# rev2.net
KiCad netlist of a schematic drawn in EAGLE
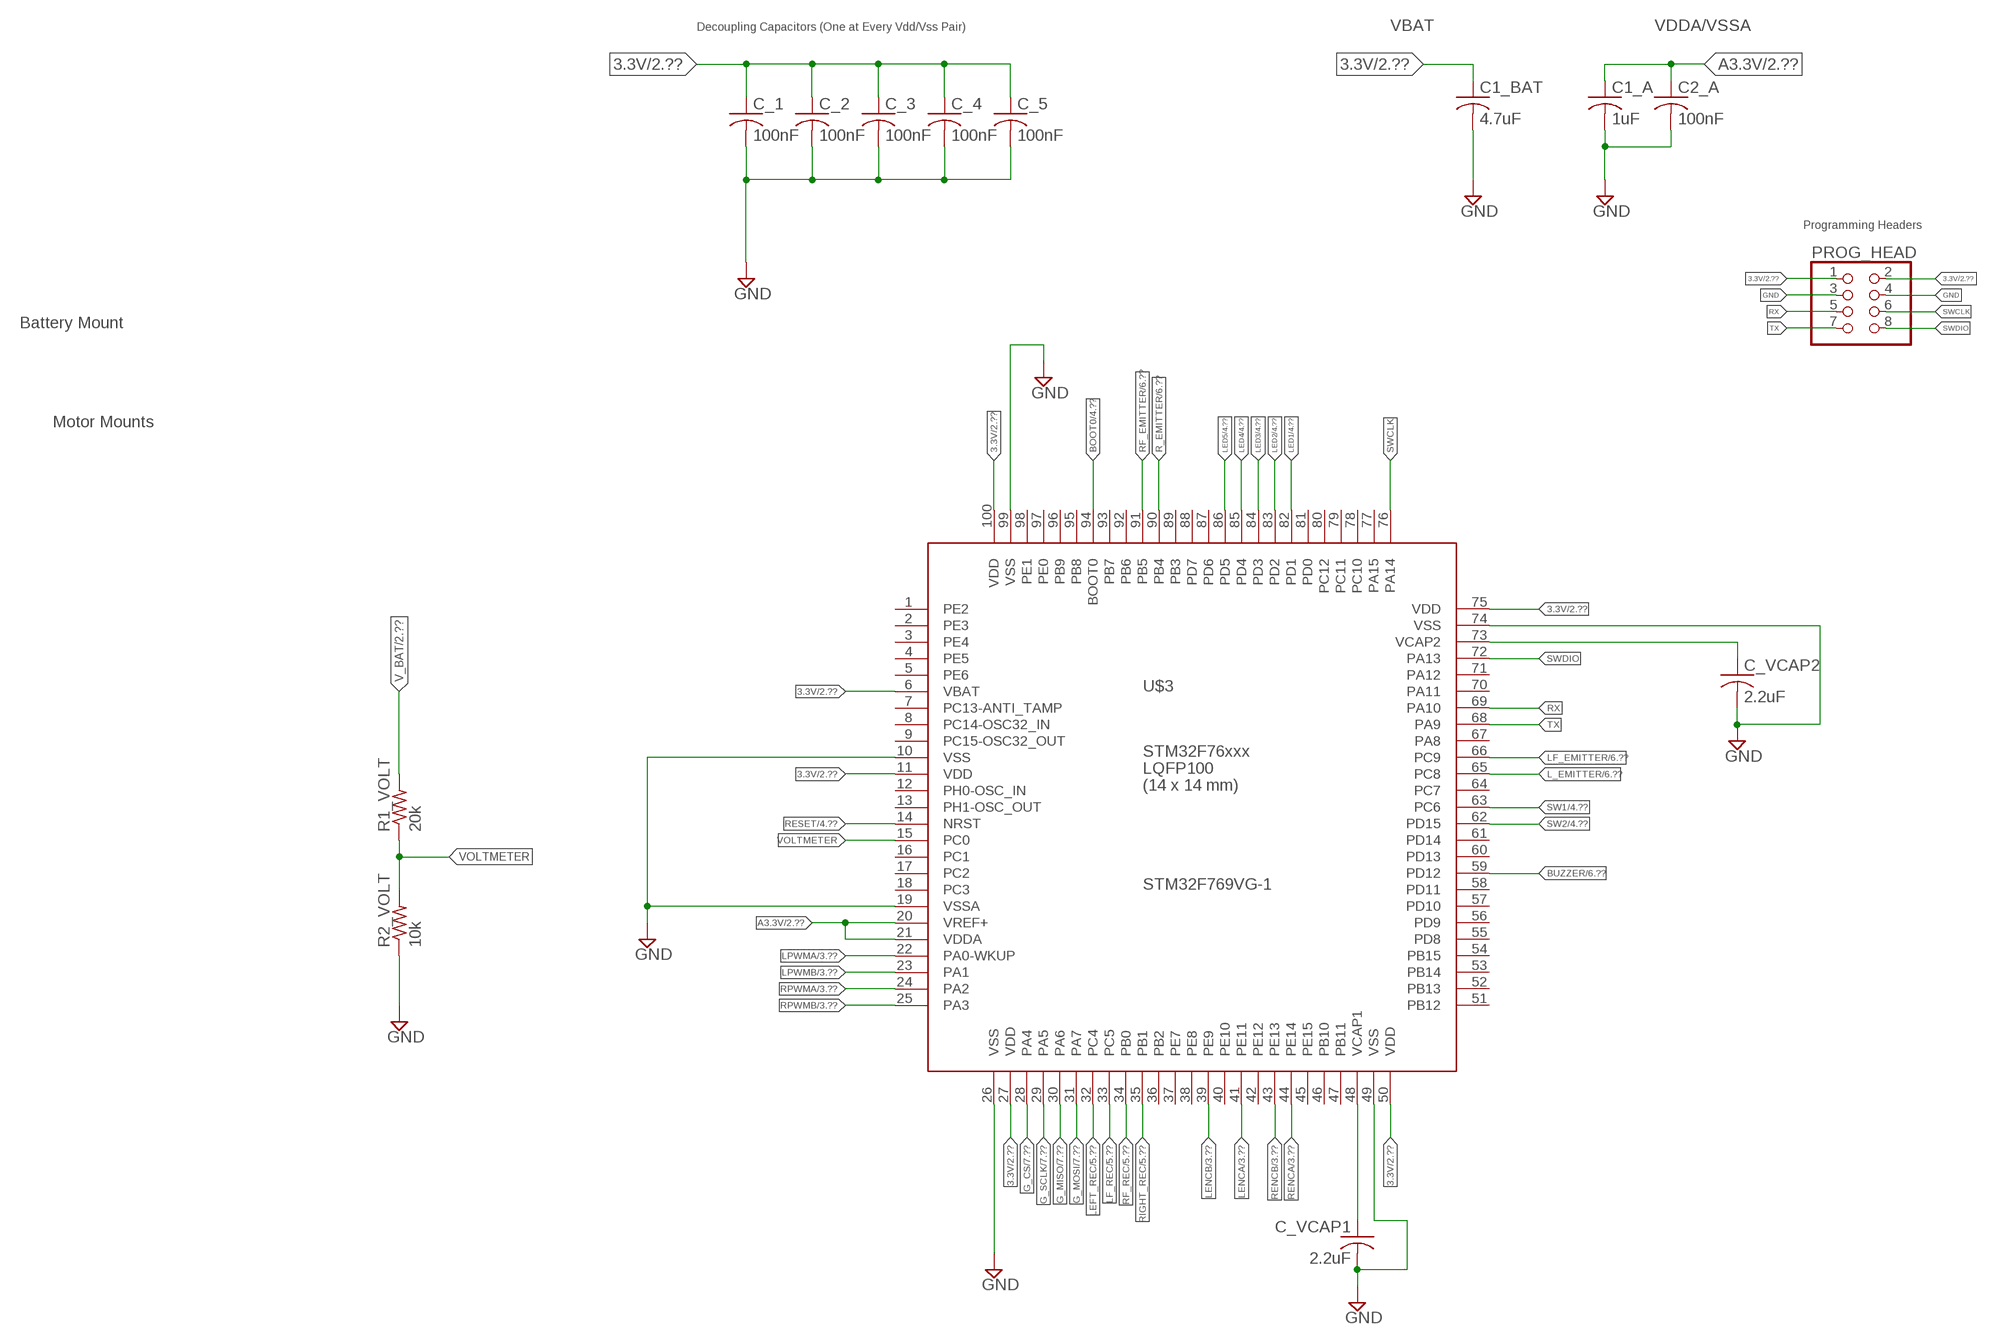
[diagram p0: schematic, sheet 1]
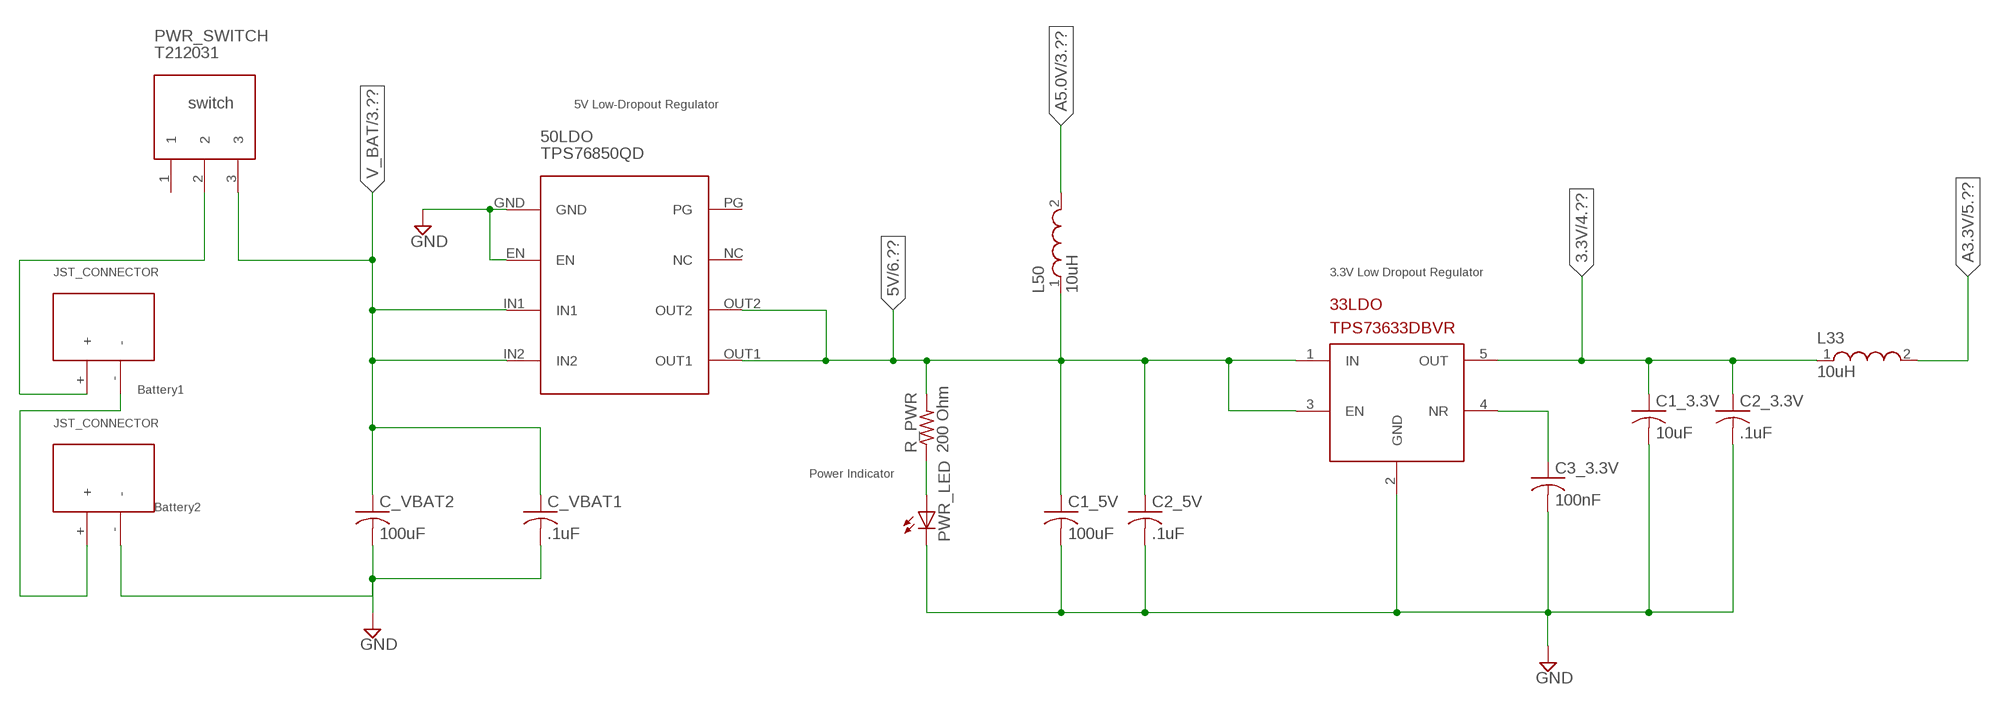
[diagram p1: schematic, sheet 2]
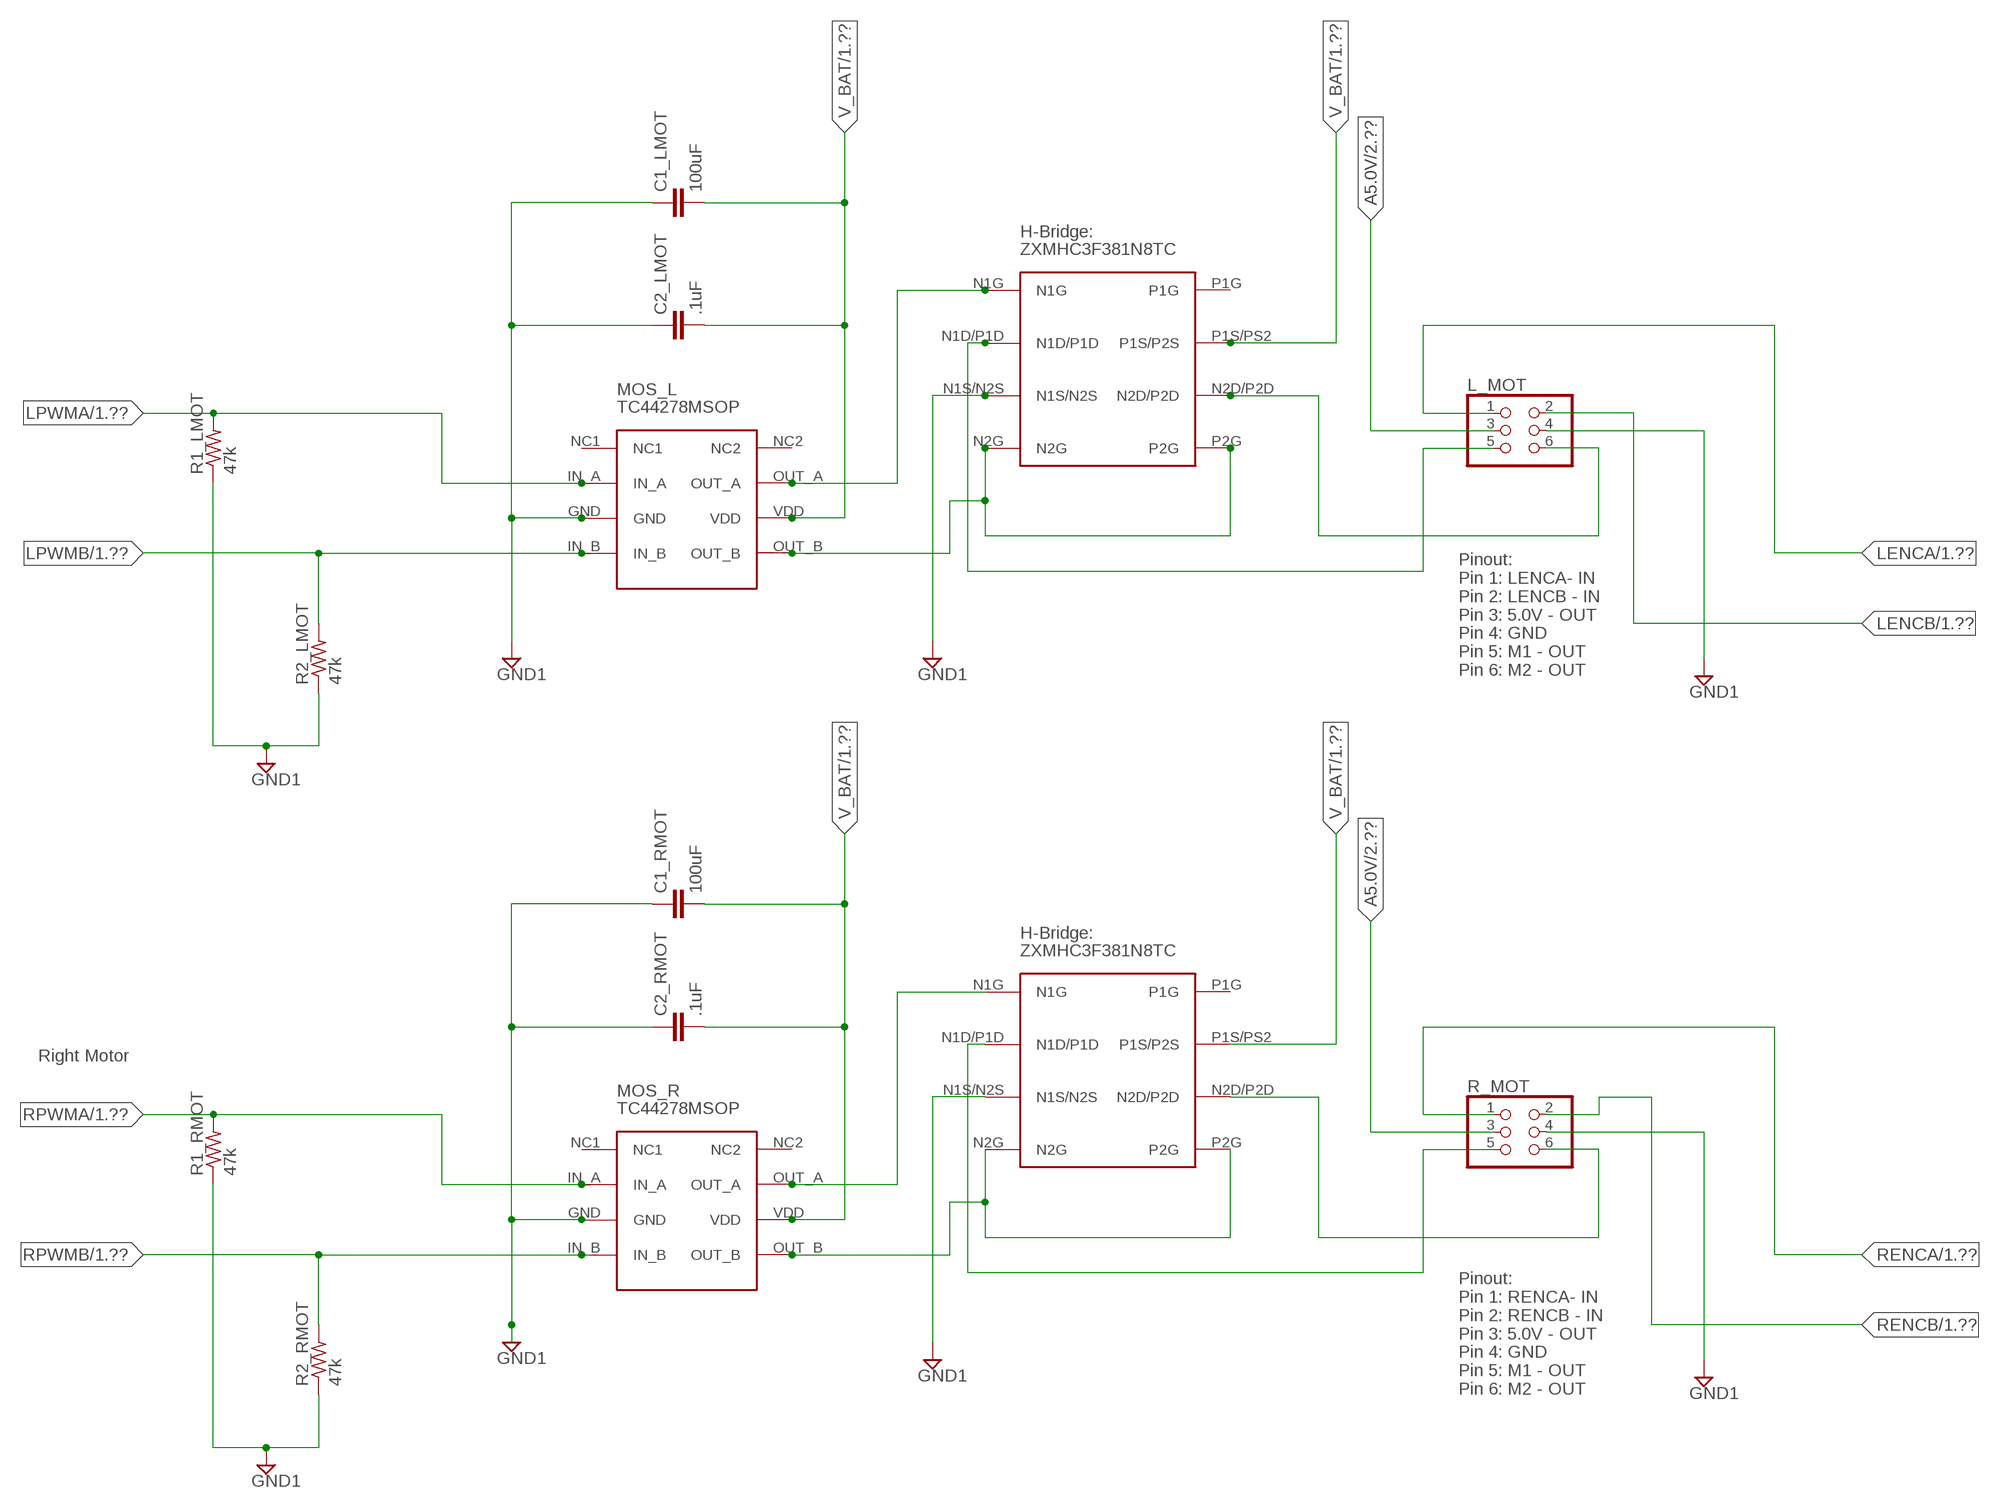
[diagram p2: schematic, sheet 3]
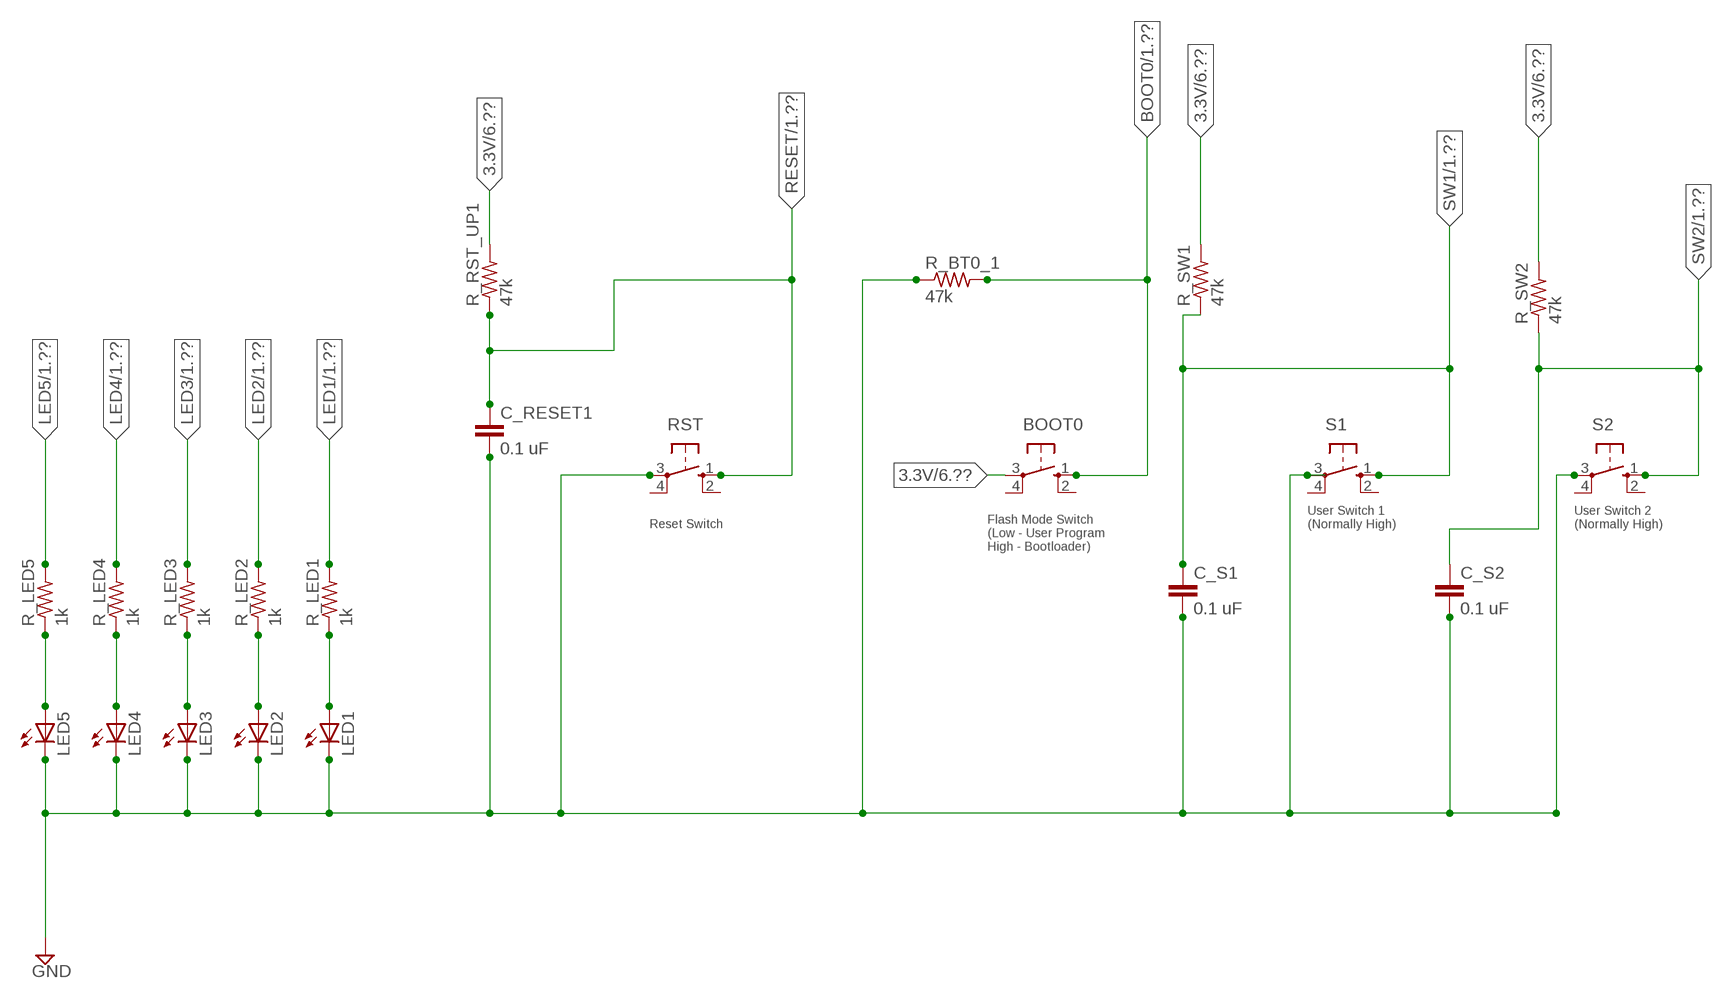
[diagram p3: schematic, sheet 4]
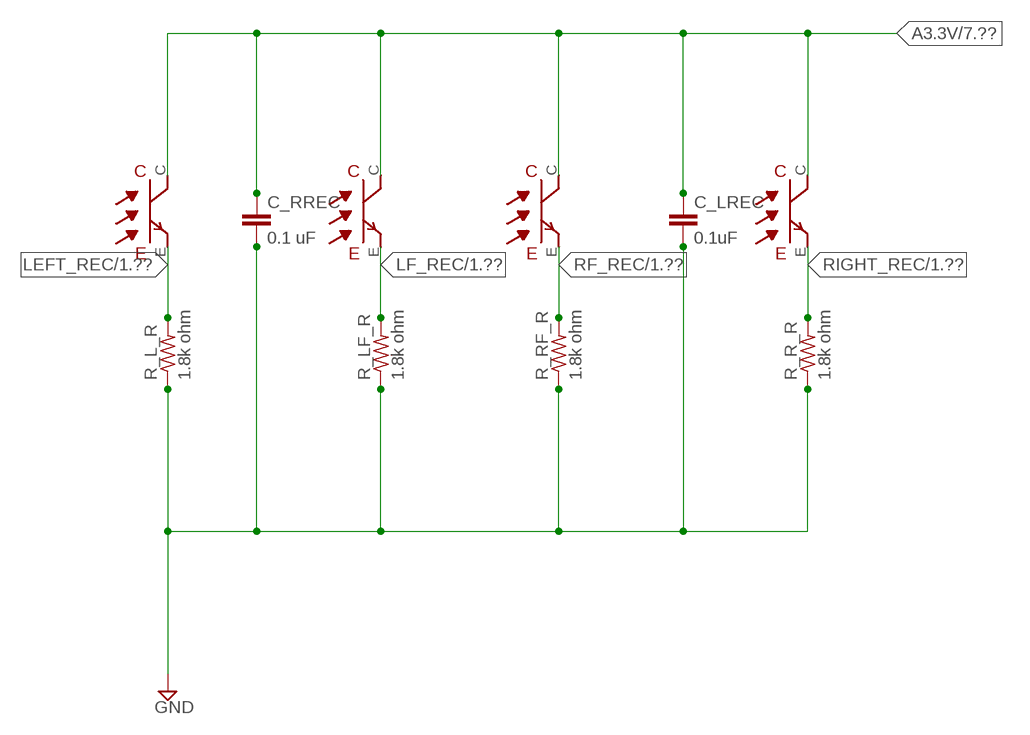
[diagram p4: schematic, sheet 5]
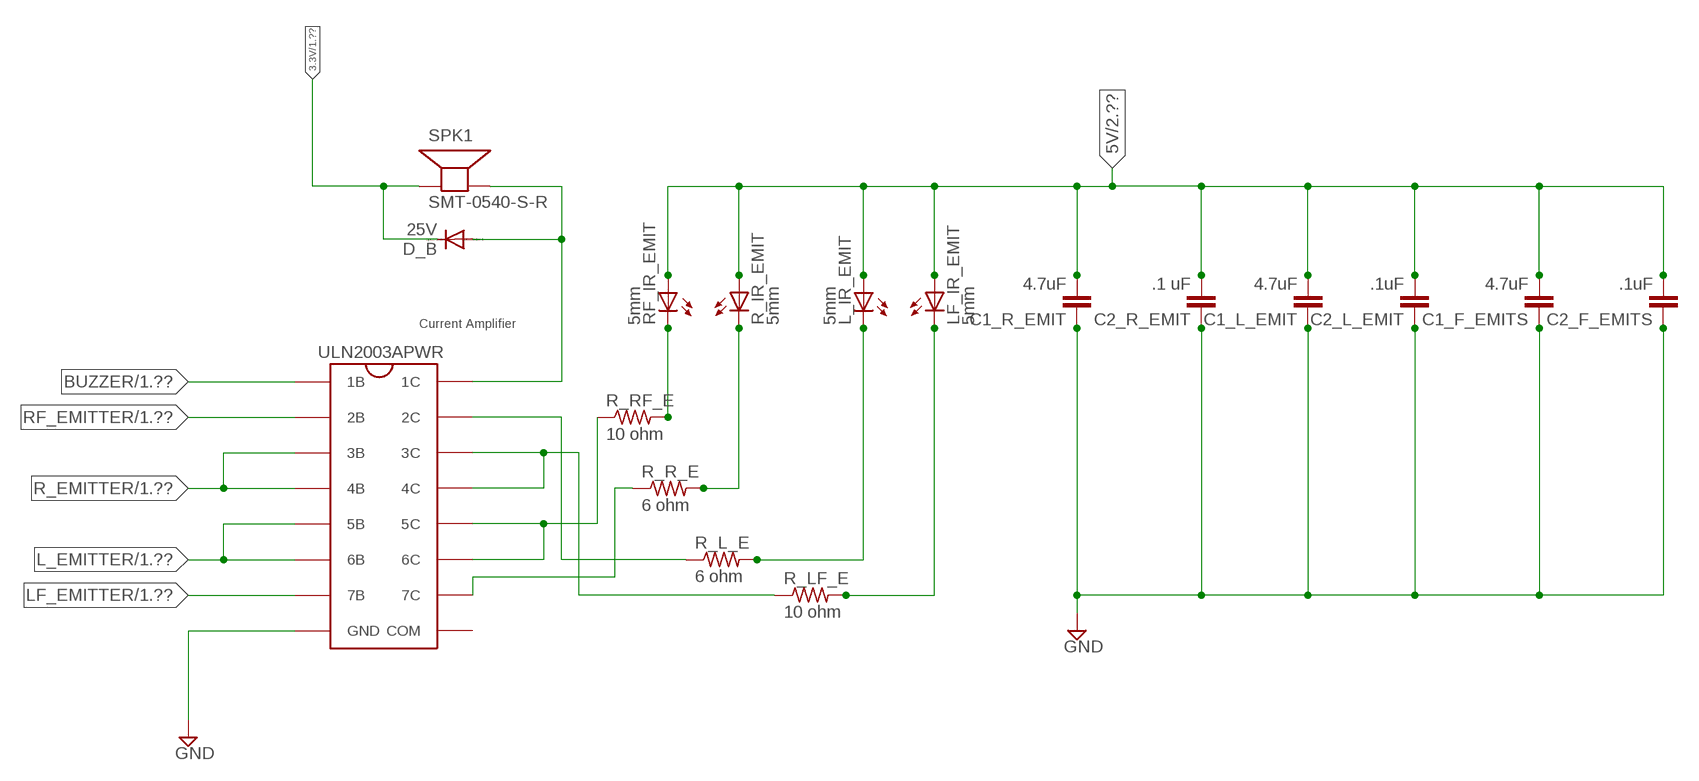
[diagram p5: schematic, sheet 6]
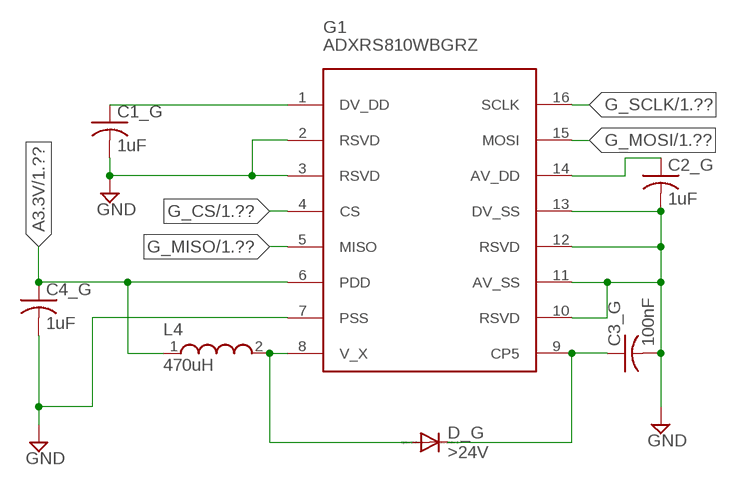
[diagram p6: schematic, sheet 7]

(export (version "E")
  (design (tool "Eeschema 10.0.6"))
  (components
    (comp (ref "C1_LMOT")
      (value "100uF")
      (footprint "eagle-import:C0805")
      (libsource (lib "eagle-import") (part "C-EUC0805"))
    )
    (comp (ref "C1_RMOT")
      (value "100uF")
      (footprint "eagle-import:C0805")
      (libsource (lib "eagle-import") (part "C-EUC0805"))
    )
    (comp (ref "C2_LMOT")
      (value ".1uF")
      (footprint "eagle-import:C0805")
      (libsource (lib "eagle-import") (part "C-EUC0805"))
    )
    (comp (ref "C2_RMOT")
      (value ".1uF")
      (footprint "eagle-import:C0805")
      (libsource (lib "eagle-import") (part "C-EUC0805"))
    )
    (comp (ref "HB_L")
      (value "ZXMHC3F381N8TC")
      (footprint "eagle-import:8-SOIC")
      (libsource (lib "eagle-import") (part "ZXMHC3F381N8TC"))
    )
    (comp (ref "HB_R")
      (value "ZXMHC3F381N8TC")
      (footprint "eagle-import:8-SOIC")
      (libsource (lib "eagle-import") (part "ZXMHC3F381N8TC"))
    )
    (comp (ref "L_MOT")
      (value "PINHD-2X3")
      (footprint "eagle-import:2X03")
      (libsource (lib "eagle-import") (part "PINHD-2X3"))
    )
    (comp (ref "MOS_L")
      (value "TC44278MSOP")
      (footprint "eagle-import:TC44278MSOP")
      (libsource (lib "eagle-import") (part "TC44278MSOP"))
    )
    (comp (ref "MOS_R")
      (value "TC44278MSOP")
      (footprint "eagle-import:TC44278MSOP")
      (libsource (lib "eagle-import") (part "TC44278MSOP"))
    )
    (comp (ref "R1_LMOT")
      (value "47k")
      (footprint "eagle-import:R0603")
      (libsource (lib "eagle-import") (part "R-US_R0603"))
    )
    (comp (ref "R1_RMOT")
      (value "47k")
      (footprint "eagle-import:R0603")
      (libsource (lib "eagle-import") (part "R-US_R0603"))
    )
    (comp (ref "R2_LMOT")
      (value "47k")
      (footprint "eagle-import:R0603")
      (libsource (lib "eagle-import") (part "R-US_R0603"))
    )
    (comp (ref "R2_RMOT")
      (value "47k")
      (footprint "eagle-import:R0603")
      (libsource (lib "eagle-import") (part "R-US_R0603"))
    )
    (comp (ref "R_MOT")
      (value "PINHD-2X3")
      (footprint "eagle-import:2X03")
      (libsource (lib "eagle-import") (part "PINHD-2X3"))
    )
    (comp (ref "C1_F_EMITS")
      (value "4.7uF")
      (footprint "eagle-import:C0603")
      (libsource (lib "eagle-import") (part "resistor_C-EUC0603"))
    )
    (comp (ref "C1_L_EMIT")
      (value "4.7uF")
      (footprint "eagle-import:C0603")
      (libsource (lib "eagle-import") (part "resistor_C-EUC0603"))
    )
    (comp (ref "C1_R_EMIT")
      (value "4.7uF")
      (footprint "eagle-import:C0603")
      (libsource (lib "eagle-import") (part "resistor_C-EUC0603"))
    )
    (comp (ref "C2_F_EMITS")
      (value ".1uF")
      (footprint "eagle-import:C0603")
      (libsource (lib "eagle-import") (part "resistor_C-EUC0603"))
    )
    (comp (ref "C2_L_EMIT")
      (value ".1uF")
      (footprint "eagle-import:C0603")
      (libsource (lib "eagle-import") (part "resistor_C-EUC0603"))
    )
    (comp (ref "C2_R_EMIT")
      (value ".1 uF")
      (footprint "eagle-import:C0603")
      (libsource (lib "eagle-import") (part "resistor_C-EUC0603"))
    )
    (comp (ref "D_B")
      (value "25V")
      (footprint "eagle-import:SOD123")
      (libsource (lib "eagle-import") (part "DIODE-SOD123"))
    )
    (comp (ref "LF_IR_EMIT")
      (value "5mm")
      (footprint "eagle-import:LED5MM")
      (libsource (lib "eagle-import") (part "LED5MM"))
    )
    (comp (ref "L_IR_EMIT")
      (value "5mm")
      (footprint "eagle-import:LED5MM")
      (libsource (lib "eagle-import") (part "LED5MM"))
    )
    (comp (ref "RF_IR_EMIT")
      (value "5mm")
      (footprint "eagle-import:LED5MM")
      (libsource (lib "eagle-import") (part "LED5MM"))
    )
    (comp (ref "R_IR_EMIT")
      (value "5mm")
      (footprint "eagle-import:LED5MM")
      (libsource (lib "eagle-import") (part "LED5MM"))
    )
    (comp (ref "R_LF_E")
      (value "10 ohm")
      (footprint "eagle-import:R0603")
      (libsource (lib "eagle-import") (part "R-US_R0603"))
    )
    (comp (ref "R_L_E")
      (value "6 ohm")
      (footprint "eagle-import:R0603")
      (libsource (lib "eagle-import") (part "R-US_R0603"))
    )
    (comp (ref "R_RF_E")
      (value "10 ohm")
      (footprint "eagle-import:R0603")
      (libsource (lib "eagle-import") (part "R-US_R0603"))
    )
    (comp (ref "R_R_E")
      (value "6 ohm")
      (footprint "eagle-import:R0603")
      (libsource (lib "eagle-import") (part "R-US_R0603"))
    )
    (comp (ref "SPK1")
      (value "SMT-0540-S-R")
      (footprint "eagle-import:SMT-0540-S-R")
      (fields (field (name "MF") "PUI Audio"))
      (libsource (lib "eagle-import") (part "SMT-0540-S-R"))
    )
    (comp (ref "U$9")
      (value "ULN2003APWR")
      (footprint "eagle-import:ULN2003APWR")
      (libsource (lib "eagle-import") (part "ULN2003APWR"))
    )
    (comp (ref "BOOT0")
      (value "10-XX")
      (footprint "eagle-import:B3F-10XX")
      (fields (field (name "MPN") "B3F-1000"))
      (libsource (lib "eagle-import") (part "10-XX"))
    )
    (comp (ref "C_RESET1")
      (value "0.1 uF")
      (footprint "eagle-import:C0603")
      (libsource (lib "eagle-import") (part "resistor_C-EUC0603"))
    )
    (comp (ref "C_S1")
      (value "0.1 uF")
      (footprint "eagle-import:C0603")
      (libsource (lib "eagle-import") (part "resistor_C-EUC0603"))
    )
    (comp (ref "C_S2")
      (value "0.1 uF")
      (footprint "eagle-import:C0603")
      (libsource (lib "eagle-import") (part "resistor_C-EUC0603"))
    )
    (comp (ref "LED1")
      (value "LEDCHIPLED_0805")
      (footprint "eagle-import:CHIPLED_0805")
      (libsource (lib "eagle-import") (part "LEDCHIPLED_0805"))
    )
    (comp (ref "LED2")
      (value "LEDCHIPLED_0805")
      (footprint "eagle-import:CHIPLED_0805")
      (libsource (lib "eagle-import") (part "LEDCHIPLED_0805"))
    )
    (comp (ref "LED3")
      (value "LEDCHIPLED_0805")
      (footprint "eagle-import:CHIPLED_0805")
      (libsource (lib "eagle-import") (part "LEDCHIPLED_0805"))
    )
    (comp (ref "LED4")
      (value "LEDCHIPLED_0805")
      (footprint "eagle-import:CHIPLED_0805")
      (libsource (lib "eagle-import") (part "LEDCHIPLED_0805"))
    )
    (comp (ref "LED5")
      (value "LEDCHIPLED_0805")
      (footprint "eagle-import:CHIPLED_0805")
      (libsource (lib "eagle-import") (part "LEDCHIPLED_0805"))
    )
    (comp (ref "RST")
      (value "10-XX")
      (footprint "eagle-import:B3F-10XX")
      (fields (field (name "MPN") "B3F-1000"))
      (libsource (lib "eagle-import") (part "10-XX"))
    )
    (comp (ref "R_BT0_1")
      (value "47k")
      (footprint "eagle-import:R0603")
      (libsource (lib "eagle-import") (part "R-US_R0603"))
    )
    (comp (ref "R_LED1")
      (value "1k")
      (footprint "eagle-import:R0603")
      (libsource (lib "eagle-import") (part "R-US_R0603"))
    )
    (comp (ref "R_LED2")
      (value "1k")
      (footprint "eagle-import:R0603")
      (libsource (lib "eagle-import") (part "R-US_R0603"))
    )
    (comp (ref "R_LED3")
      (value "1k")
      (footprint "eagle-import:R0603")
      (libsource (lib "eagle-import") (part "R-US_R0603"))
    )
    (comp (ref "R_LED4")
      (value "1k")
      (footprint "eagle-import:R0603")
      (libsource (lib "eagle-import") (part "R-US_R0603"))
    )
    (comp (ref "R_LED5")
      (value "1k")
      (footprint "eagle-import:R0603")
      (libsource (lib "eagle-import") (part "R-US_R0603"))
    )
    (comp (ref "R_RST_UP1")
      (value "47k")
      (footprint "eagle-import:R0603")
      (libsource (lib "eagle-import") (part "R-US_R0603"))
    )
    (comp (ref "R_SW1")
      (value "47k")
      (footprint "eagle-import:R0603")
      (libsource (lib "eagle-import") (part "R-US_R0603"))
    )
    (comp (ref "R_SW2")
      (value "47k")
      (footprint "eagle-import:R0603")
      (libsource (lib "eagle-import") (part "R-US_R0603"))
    )
    (comp (ref "S1")
      (value "10-XX")
      (footprint "eagle-import:B3F-10XX")
      (fields (field (name "MPN") "B3F-1000"))
      (libsource (lib "eagle-import") (part "10-XX"))
    )
    (comp (ref "S2")
      (value "10-XX")
      (footprint "eagle-import:B3F-10XX")
      (fields (field (name "MPN") "B3F-1000"))
      (libsource (lib "eagle-import") (part "10-XX"))
    )
    (comp (ref "C1_A")
      (value "1uF")
      (footprint "eagle-import:C0603")
      (libsource (lib "eagle-import") (part "C-USC0603"))
    )
    (comp (ref "C1_BAT")
      (value "4.7uF")
      (footprint "eagle-import:C0603")
      (libsource (lib "eagle-import") (part "C-USC0603"))
    )
    (comp (ref "C2_A")
      (value "100nF")
      (footprint "eagle-import:C0603")
      (libsource (lib "eagle-import") (part "C-USC0603"))
    )
    (comp (ref "C_1")
      (value "100nF")
      (footprint "eagle-import:C0603")
      (libsource (lib "eagle-import") (part "C-USC0603"))
    )
    (comp (ref "C_2")
      (value "100nF")
      (footprint "eagle-import:C0603")
      (libsource (lib "eagle-import") (part "C-USC0603"))
    )
    (comp (ref "C_3")
      (value "100nF")
      (footprint "eagle-import:C0603")
      (libsource (lib "eagle-import") (part "C-USC0603"))
    )
    (comp (ref "C_4")
      (value "100nF")
      (footprint "eagle-import:C0603")
      (libsource (lib "eagle-import") (part "C-USC0603"))
    )
    (comp (ref "C_5")
      (value "100nF")
      (footprint "eagle-import:C0603")
      (libsource (lib "eagle-import") (part "C-USC0603"))
    )
    (comp (ref "C_VCAP1")
      (value "2.2uF")
      (footprint "eagle-import:C0603")
      (libsource (lib "eagle-import") (part "C-USC0603"))
    )
    (comp (ref "C_VCAP2")
      (value "2.2uF")
      (footprint "eagle-import:C0603")
      (libsource (lib "eagle-import") (part "C-USC0603"))
    )
    (comp (ref "PROG_HEAD")
      (value "PINHD-2X4")
      (footprint "eagle-import:2X04")
      (libsource (lib "eagle-import") (part "PINHD-2X4"))
    )
    (comp (ref "R1_VOLT")
      (value "20k")
      (footprint "eagle-import:R0603")
      (libsource (lib "eagle-import") (part "R-US_R0603"))
    )
    (comp (ref "R2_VOLT")
      (value "10k")
      (footprint "eagle-import:R0603")
      (libsource (lib "eagle-import") (part "R-US_R0603"))
    )
    (comp (ref "U$2")
      (value "MOTOR")
      (footprint "eagle-import:MOTOR_MOUNT")
      (libsource (lib "eagle-import") (part "MOTOR"))
    )
    (comp (ref "U$3")
      (value "STM32F769VG-1")
      (footprint "eagle-import:LQFP100")
      (libsource (lib "eagle-import") (part "STM32F769VG-1"))
    )
    (comp (ref "U$5")
      (value "MOTOR")
      (footprint "eagle-import:MOTOR_MOUNT")
      (libsource (lib "eagle-import") (part "MOTOR"))
    )
    (comp (ref "C1_G")
      (value "1uF")
      (footprint "eagle-import:C0603")
      (libsource (lib "eagle-import") (part "C-USC0603"))
    )
    (comp (ref "C2_G")
      (value "1uF")
      (footprint "eagle-import:C0603")
      (libsource (lib "eagle-import") (part "C-USC0603"))
    )
    (comp (ref "C3_G")
      (value "100nF")
      (footprint "eagle-import:C0603")
      (libsource (lib "eagle-import") (part "C-USC0603"))
    )
    (comp (ref "C4_G")
      (value "1uF")
      (footprint "eagle-import:C0603")
      (libsource (lib "eagle-import") (part "C-USC0603"))
    )
    (comp (ref "D_G")
      (value ">24V")
      (footprint "eagle-import:SOD123")
      (libsource (lib "eagle-import") (part "DIODE-SOD123"))
    )
    (comp (ref "G1")
      (value "ADXRS810")
      (footprint "eagle-import:SOIC-16")
      (libsource (lib "eagle-import") (part "ADXRS810"))
    )
    (comp (ref "L4")
      (value "470uH")
      (footprint "eagle-import:WE-MI_0805")
      (libsource (lib "eagle-import") (part "WE-MI_0805"))
    )
    (comp (ref "33LDO")
      (value "TPS73633DBVR")
      (footprint "eagle-import:SOT23-DBV")
      (fields (field (name "MF") "Texas Instruments"))
      (libsource (lib "eagle-import") (part "TPS73633DBVR"))
    )
    (comp (ref "50LDO")
      (value "TPS76850QD")
      (footprint "eagle-import:8-SOIC(SMT)")
      (libsource (lib "eagle-import") (part "TPS76850"))
    )
    (comp (ref "C1_3.3V")
      (value "10uF")
      (footprint "eagle-import:C0603")
      (libsource (lib "eagle-import") (part "resistor_C-USC0603"))
    )
    (comp (ref "C1_5V")
      (value "100uF")
      (footprint "eagle-import:C0603")
      (libsource (lib "eagle-import") (part "resistor_C-USC0603"))
    )
    (comp (ref "C2_3.3V")
      (value ".1uF")
      (footprint "eagle-import:C0603")
      (libsource (lib "eagle-import") (part "resistor_C-USC0603"))
    )
    (comp (ref "C2_5V")
      (value ".1uF")
      (footprint "eagle-import:C0603")
      (libsource (lib "eagle-import") (part "resistor_C-USC0603"))
    )
    (comp (ref "C3_3.3V")
      (value "100nF")
      (footprint "eagle-import:C0603")
      (libsource (lib "eagle-import") (part "resistor_C-USC0603"))
    )
    (comp (ref "C_VBAT1")
      (value ".1uF")
      (footprint "eagle-import:C0603")
      (libsource (lib "eagle-import") (part "resistor_C-USC0603"))
    )
    (comp (ref "C_VBAT2")
      (value "100uF")
      (footprint "eagle-import:C1206")
      (libsource (lib "eagle-import") (part "resistor_C-USC1206"))
    )
    (comp (ref "L33")
      (value "10uH")
      (footprint "eagle-import:WE-MI_0805")
      (libsource (lib "eagle-import") (part "WE-MI_0805"))
    )
    (comp (ref "L50")
      (value "10uH")
      (footprint "eagle-import:WE-MI_0805")
      (libsource (lib "eagle-import") (part "WE-MI_0805"))
    )
    (comp (ref "PWR_LED")
      (value "LEDCHIPLED_0805")
      (footprint "eagle-import:CHIPLED_0805")
      (libsource (lib "eagle-import") (part "LEDCHIPLED_0805"))
    )
    (comp (ref "PWR_SWITCH")
      (value "T212031")
      (footprint "eagle-import:T212031")
      (libsource (lib "eagle-import") (part "T212031"))
    )
    (comp (ref "R_PWR")
      (value "200 Ohm")
      (footprint "eagle-import:R0603")
      (libsource (lib "eagle-import") (part "R-US_R0603"))
    )
    (comp (ref "U$7")
      (value "JST_CONNECTOR_FEMALE")
      (footprint "eagle-import:JST_CONNECTOR_FEMALE")
      (libsource (lib "eagle-import") (part "JST_CONNECTOR_FEMALE"))
    )
    (comp (ref "U$8")
      (value "JST_CONNECTOR_FEMALE")
      (footprint "eagle-import:JST_CONNECTOR_FEMALE")
      (libsource (lib "eagle-import") (part "JST_CONNECTOR_FEMALE"))
    )
    (comp (ref "C_LREC")
      (value "0.1uF")
      (footprint "eagle-import:C0603")
      (libsource (lib "eagle-import") (part "resistor_C-EUC0603"))
    )
    (comp (ref "C_RREC")
      (value "0.1 uF")
      (footprint "eagle-import:C0603")
      (libsource (lib "eagle-import") (part "resistor_C-EUC0603"))
    )
    (comp (ref "LF_REC")
      (value "RECEIVER")
      (footprint "eagle-import:RECEIVER")
      (libsource (lib "eagle-import") (part "RECEIVER"))
    )
    (comp (ref "L_REC")
      (value "RECEIVER")
      (footprint "eagle-import:RECEIVER")
      (libsource (lib "eagle-import") (part "RECEIVER"))
    )
    (comp (ref "RF_REC")
      (value "RECEIVER")
      (footprint "eagle-import:RECEIVER")
      (libsource (lib "eagle-import") (part "RECEIVER"))
    )
    (comp (ref "R_LF_R")
      (value "1.8k ohm")
      (footprint "eagle-import:R0603")
      (libsource (lib "eagle-import") (part "R-US_R0603"))
    )
    (comp (ref "R_L_R")
      (value "1.8k ohm")
      (footprint "eagle-import:R0603")
      (libsource (lib "eagle-import") (part "R-US_R0603"))
    )
    (comp (ref "R_REC")
      (value "RECEIVER")
      (footprint "eagle-import:RECEIVER")
      (libsource (lib "eagle-import") (part "RECEIVER"))
    )
    (comp (ref "R_RF_R")
      (value "1.8k ohm")
      (footprint "eagle-import:R0603")
      (libsource (lib "eagle-import") (part "R-US_R0603"))
    )
    (comp (ref "R_R_R")
      (value "1.8k ohm")
      (footprint "eagle-import:R0603")
      (libsource (lib "eagle-import") (part "R-US_R0603"))
    )
  )
  (nets
    (net (code "1") (name "3.3V") (class "Default")
      (node (ref "33LDO") (pin "5") (pinfunction "OUT_5") (pintype "bidirectional"))
      (node (ref "BOOT0") (pin "3") (pinfunction "P_3") (pintype "passive"))
      (node (ref "C1_3.3V") (pin "1") (pinfunction "1_1") (pintype "passive"))
      (node (ref "C1_BAT") (pin "1") (pinfunction "1_1") (pintype "passive"))
      (node (ref "C2_3.3V") (pin "1") (pinfunction "1_1") (pintype "passive"))
      (node (ref "C_1") (pin "1") (pinfunction "1_1") (pintype "passive"))
      (node (ref "C_2") (pin "1") (pinfunction "1_1") (pintype "passive"))
      (node (ref "C_3") (pin "1") (pinfunction "1_1") (pintype "passive"))
      (node (ref "C_4") (pin "1") (pinfunction "1_1") (pintype "passive"))
      (node (ref "C_5") (pin "1") (pinfunction "1_1") (pintype "passive"))
      (node (ref "D_B") (pin "C") (pinfunction "C_C") (pintype "passive"))
      (node (ref "L33") (pin "1") (pinfunction "1_1") (pintype "passive"))
      (node (ref "PROG_HEAD") (pin "1") (pinfunction "1_1") (pintype "passive"))
      (node (ref "PROG_HEAD") (pin "2") (pinfunction "2_2") (pintype "passive"))
      (node (ref "R_RST_UP1") (pin "2") (pinfunction "2_2") (pintype "passive"))
      (node (ref "R_SW1") (pin "2") (pinfunction "2_2") (pintype "passive"))
      (node (ref "R_SW2") (pin "2") (pinfunction "2_2") (pintype "passive"))
      (node (ref "SPK1") (pin "-") (pinfunction "+_-") (pintype "passive"))
      (node (ref "U$3") (pin "100") (pinfunction "VDD_100") (pintype "bidirectional"))
      (node (ref "U$3") (pin "11") (pinfunction "VDD_11") (pintype "bidirectional"))
      (node (ref "U$3") (pin "27") (pinfunction "VDD_27") (pintype "bidirectional"))
      (node (ref "U$3") (pin "50") (pinfunction "VDD_50") (pintype "bidirectional"))
      (node (ref "U$3") (pin "6") (pinfunction "VBAT_6") (pintype "bidirectional"))
      (node (ref "U$3") (pin "75") (pinfunction "VDD_75") (pintype "bidirectional"))
    )
    (net (code "2") (name "5V") (class "Default")
      (node (ref "33LDO") (pin "1") (pinfunction "IN_1") (pintype "bidirectional"))
      (node (ref "33LDO") (pin "3") (pinfunction "EN_3") (pintype "bidirectional"))
      (node (ref "50LDO") (pin "OUT1") (pinfunction "OUT1_OUT1") (pintype "bidirectional"))
      (node (ref "50LDO") (pin "OUT2") (pinfunction "OUT2_OUT2") (pintype "bidirectional"))
      (node (ref "C1_5V") (pin "1") (pinfunction "1_1") (pintype "passive"))
      (node (ref "C1_F_EMITS") (pin "2") (pinfunction "2_2") (pintype "passive"))
      (node (ref "C1_L_EMIT") (pin "2") (pinfunction "2_2") (pintype "passive"))
      (node (ref "C1_R_EMIT") (pin "2") (pinfunction "2_2") (pintype "passive"))
      (node (ref "C2_5V") (pin "1") (pinfunction "1_1") (pintype "passive"))
      (node (ref "C2_F_EMITS") (pin "2") (pinfunction "2_2") (pintype "passive"))
      (node (ref "C2_L_EMIT") (pin "2") (pinfunction "2_2") (pintype "passive"))
      (node (ref "C2_R_EMIT") (pin "2") (pinfunction "2_2") (pintype "passive"))
      (node (ref "L50") (pin "1") (pinfunction "1_1") (pintype "passive"))
      (node (ref "LF_IR_EMIT") (pin "A") (pinfunction "A_A") (pintype "passive"))
      (node (ref "L_IR_EMIT") (pin "A") (pinfunction "A_A") (pintype "passive"))
      (node (ref "RF_IR_EMIT") (pin "A") (pinfunction "A_A") (pintype "passive"))
      (node (ref "R_IR_EMIT") (pin "A") (pinfunction "A_A") (pintype "passive"))
      (node (ref "R_PWR") (pin "2") (pinfunction "2_2") (pintype "passive"))
    )
    (net (code "3") (name "A3.3V") (class "Default")
      (node (ref "C1_A") (pin "1") (pinfunction "1_1") (pintype "passive"))
      (node (ref "C2_A") (pin "1") (pinfunction "1_1") (pintype "passive"))
      (node (ref "C4_G") (pin "1") (pinfunction "1_1") (pintype "passive"))
      (node (ref "C_LREC") (pin "1") (pinfunction "1_1") (pintype "passive"))
      (node (ref "C_RREC") (pin "1") (pinfunction "1_1") (pintype "passive"))
      (node (ref "G1") (pin "6") (pinfunction "PDD_6") (pintype "bidirectional"))
      (node (ref "L33") (pin "2") (pinfunction "2_2") (pintype "passive"))
      (node (ref "L4") (pin "1") (pinfunction "1_1") (pintype "passive"))
      (node (ref "LF_REC") (pin "C") (pinfunction "C_C") (pintype "bidirectional"))
      (node (ref "L_REC") (pin "C") (pinfunction "C_C") (pintype "bidirectional"))
      (node (ref "RF_REC") (pin "C") (pinfunction "C_C") (pintype "bidirectional"))
      (node (ref "R_REC") (pin "C") (pinfunction "C_C") (pintype "bidirectional"))
      (node (ref "U$3") (pin "20") (pinfunction "VREF+_20") (pintype "bidirectional"))
      (node (ref "U$3") (pin "21") (pinfunction "VDDA_21") (pintype "bidirectional"))
    )
    (net (code "4") (name "A5.0V") (class "Default")
      (node (ref "L50") (pin "2") (pinfunction "2_2") (pintype "passive"))
      (node (ref "L_MOT") (pin "3") (pinfunction "3_3") (pintype "passive"))
      (node (ref "R_MOT") (pin "3") (pinfunction "3_3") (pintype "passive"))
    )
    (net (code "5") (name "BOOT0") (class "Default")
      (node (ref "BOOT0") (pin "1") (pinfunction "S_1") (pintype "passive"))
      (node (ref "R_BT0_1") (pin "2") (pinfunction "2_2") (pintype "passive"))
      (node (ref "U$3") (pin "94") (pinfunction "BOOT0_94") (pintype "bidirectional"))
    )
    (net (code "6") (name "BUZZER") (class "Default")
      (node (ref "U$3") (pin "59") (pinfunction "PD12_59") (pintype "bidirectional"))
      (node (ref "U$9") (pin "1B") (pinfunction "1B_1B") (pintype "bidirectional"))
    )
    (net (code "7") (name "GND") (class "Default")
      (node (ref "33LDO") (pin "2") (pinfunction "GND_2") (pintype "bidirectional"))
      (node (ref "50LDO") (pin "EN") (pinfunction "EN_EN") (pintype "bidirectional"))
      (node (ref "50LDO") (pin "GND") (pinfunction "GND_GND") (pintype "bidirectional"))
      (node (ref "C1_3.3V") (pin "2") (pinfunction "2_2") (pintype "passive"))
      (node (ref "C1_5V") (pin "2") (pinfunction "2_2") (pintype "passive"))
      (node (ref "C1_A") (pin "2") (pinfunction "2_2") (pintype "passive"))
      (node (ref "C1_BAT") (pin "2") (pinfunction "2_2") (pintype "passive"))
      (node (ref "C1_F_EMITS") (pin "1") (pinfunction "1_1") (pintype "passive"))
      (node (ref "C1_G") (pin "2") (pinfunction "2_2") (pintype "passive"))
      (node (ref "C1_LMOT") (pin "1") (pinfunction "1_1") (pintype "passive"))
      (node (ref "C1_L_EMIT") (pin "1") (pinfunction "1_1") (pintype "passive"))
      (node (ref "C1_RMOT") (pin "1") (pinfunction "1_1") (pintype "passive"))
      (node (ref "C1_R_EMIT") (pin "1") (pinfunction "1_1") (pintype "passive"))
      (node (ref "C2_3.3V") (pin "2") (pinfunction "2_2") (pintype "passive"))
      (node (ref "C2_5V") (pin "2") (pinfunction "2_2") (pintype "passive"))
      (node (ref "C2_A") (pin "2") (pinfunction "2_2") (pintype "passive"))
      (node (ref "C2_F_EMITS") (pin "1") (pinfunction "1_1") (pintype "passive"))
      (node (ref "C2_G") (pin "2") (pinfunction "2_2") (pintype "passive"))
      (node (ref "C2_LMOT") (pin "1") (pinfunction "1_1") (pintype "passive"))
      (node (ref "C2_L_EMIT") (pin "1") (pinfunction "1_1") (pintype "passive"))
      (node (ref "C2_RMOT") (pin "1") (pinfunction "1_1") (pintype "passive"))
      (node (ref "C2_R_EMIT") (pin "1") (pinfunction "1_1") (pintype "passive"))
      (node (ref "C3_3.3V") (pin "2") (pinfunction "2_2") (pintype "passive"))
      (node (ref "C3_G") (pin "2") (pinfunction "2_2") (pintype "passive"))
      (node (ref "C4_G") (pin "2") (pinfunction "2_2") (pintype "passive"))
      (node (ref "C_1") (pin "2") (pinfunction "2_2") (pintype "passive"))
      (node (ref "C_2") (pin "2") (pinfunction "2_2") (pintype "passive"))
      (node (ref "C_3") (pin "2") (pinfunction "2_2") (pintype "passive"))
      (node (ref "C_4") (pin "2") (pinfunction "2_2") (pintype "passive"))
      (node (ref "C_5") (pin "2") (pinfunction "2_2") (pintype "passive"))
      (node (ref "C_LREC") (pin "2") (pinfunction "2_2") (pintype "passive"))
      (node (ref "C_RESET1") (pin "2") (pinfunction "2_2") (pintype "passive"))
      (node (ref "C_RREC") (pin "2") (pinfunction "2_2") (pintype "passive"))
      (node (ref "C_S1") (pin "2") (pinfunction "2_2") (pintype "passive"))
      (node (ref "C_S2") (pin "2") (pinfunction "2_2") (pintype "passive"))
      (node (ref "C_VBAT1") (pin "2") (pinfunction "2_2") (pintype "passive"))
      (node (ref "C_VBAT2") (pin "2") (pinfunction "2_2") (pintype "passive"))
      (node (ref "C_VCAP1") (pin "2") (pinfunction "2_2") (pintype "passive"))
      (node (ref "C_VCAP2") (pin "2") (pinfunction "2_2") (pintype "passive"))
      (node (ref "G1") (pin "10") (pinfunction "RSVD_10") (pintype "bidirectional"))
      (node (ref "G1") (pin "11") (pinfunction "AV_SS_11") (pintype "bidirectional"))
      (node (ref "G1") (pin "12") (pinfunction "RSVD_12") (pintype "bidirectional"))
      (node (ref "G1") (pin "13") (pinfunction "DV_SS_13") (pintype "bidirectional"))
      (node (ref "G1") (pin "2") (pinfunction "RSVD_2") (pintype "bidirectional"))
      (node (ref "G1") (pin "3") (pinfunction "RSVD_3") (pintype "bidirectional"))
      (node (ref "G1") (pin "7") (pinfunction "PSS_7") (pintype "bidirectional"))
      (node (ref "HB_L") (pin "N1S/N2S") (pinfunction "N1S/N2S_N1S/N2S") (pintype "bidirectional"))
      (node (ref "HB_R") (pin "N1S/N2S") (pinfunction "N1S/N2S_N1S/N2S") (pintype "bidirectional"))
      (node (ref "LED1") (pin "C") (pinfunction "C_C") (pintype "passive"))
      (node (ref "LED2") (pin "C") (pinfunction "C_C") (pintype "passive"))
      (node (ref "LED3") (pin "C") (pinfunction "C_C") (pintype "passive"))
      (node (ref "LED4") (pin "C") (pinfunction "C_C") (pintype "passive"))
      (node (ref "LED5") (pin "C") (pinfunction "C_C") (pintype "passive"))
      (node (ref "L_MOT") (pin "4") (pinfunction "4_4") (pintype "passive"))
      (node (ref "MOS_L") (pin "GND") (pinfunction "GND_GND") (pintype "bidirectional"))
      (node (ref "MOS_R") (pin "GND") (pinfunction "GND_GND") (pintype "bidirectional"))
      (node (ref "PROG_HEAD") (pin "3") (pinfunction "3_3") (pintype "passive"))
      (node (ref "PROG_HEAD") (pin "4") (pinfunction "4_4") (pintype "passive"))
      (node (ref "PWR_LED") (pin "C") (pinfunction "C_C") (pintype "passive"))
      (node (ref "R1_LMOT") (pin "1") (pinfunction "1_1") (pintype "passive"))
      (node (ref "R1_RMOT") (pin "1") (pinfunction "1_1") (pintype "passive"))
      (node (ref "R2_LMOT") (pin "1") (pinfunction "1_1") (pintype "passive"))
      (node (ref "R2_RMOT") (pin "1") (pinfunction "1_1") (pintype "passive"))
      (node (ref "R2_VOLT") (pin "1") (pinfunction "1_1") (pintype "passive"))
      (node (ref "RST") (pin "3") (pinfunction "P_3") (pintype "passive"))
      (node (ref "R_BT0_1") (pin "1") (pinfunction "1_1") (pintype "passive"))
      (node (ref "R_LF_R") (pin "1") (pinfunction "1_1") (pintype "passive"))
      (node (ref "R_L_R") (pin "1") (pinfunction "1_1") (pintype "passive"))
      (node (ref "R_MOT") (pin "4") (pinfunction "4_4") (pintype "passive"))
      (node (ref "R_RF_R") (pin "1") (pinfunction "1_1") (pintype "passive"))
      (node (ref "R_R_R") (pin "1") (pinfunction "1_1") (pintype "passive"))
      (node (ref "S1") (pin "3") (pinfunction "P_3") (pintype "passive"))
      (node (ref "S2") (pin "3") (pinfunction "P_3") (pintype "passive"))
      (node (ref "U$3") (pin "10") (pinfunction "VSS_10") (pintype "bidirectional"))
      (node (ref "U$3") (pin "19") (pinfunction "VSSA_19") (pintype "bidirectional"))
      (node (ref "U$3") (pin "26") (pinfunction "VSS_26") (pintype "bidirectional"))
      (node (ref "U$3") (pin "49") (pinfunction "VSS_49") (pintype "bidirectional"))
      (node (ref "U$3") (pin "74") (pinfunction "VSS_74") (pintype "bidirectional"))
      (node (ref "U$3") (pin "99") (pinfunction "VSS_99") (pintype "bidirectional"))
      (node (ref "U$8") (pin "-") (pinfunction "-_-") (pintype "bidirectional"))
      (node (ref "U$9") (pin "GND") (pinfunction "GND_GND") (pintype "bidirectional"))
    )
    (net (code "8") (name "G_CS") (class "Default")
      (node (ref "G1") (pin "4") (pinfunction "CS_4") (pintype "bidirectional"))
      (node (ref "U$3") (pin "28") (pinfunction "PA4_28") (pintype "bidirectional"))
    )
    (net (code "9") (name "G_MISO") (class "Default")
      (node (ref "G1") (pin "5") (pinfunction "MISO_5") (pintype "bidirectional"))
      (node (ref "U$3") (pin "30") (pinfunction "PA6_30") (pintype "bidirectional"))
    )
    (net (code "10") (name "G_MOSI") (class "Default")
      (node (ref "G1") (pin "15") (pinfunction "MOSI_15") (pintype "bidirectional"))
      (node (ref "U$3") (pin "31") (pinfunction "PA7_31") (pintype "bidirectional"))
    )
    (net (code "11") (name "G_SCLK") (class "Default")
      (node (ref "G1") (pin "16") (pinfunction "SCLK_16") (pintype "bidirectional"))
      (node (ref "U$3") (pin "29") (pinfunction "PA5_29") (pintype "bidirectional"))
    )
    (net (code "12") (name "LED1") (class "Default")
      (node (ref "R_LED1") (pin "2") (pinfunction "2_2") (pintype "passive"))
      (node (ref "U$3") (pin "82") (pinfunction "PD1_82") (pintype "bidirectional"))
    )
    (net (code "13") (name "LED2") (class "Default")
      (node (ref "R_LED2") (pin "2") (pinfunction "2_2") (pintype "passive"))
      (node (ref "U$3") (pin "83") (pinfunction "PD2_83") (pintype "bidirectional"))
    )
    (net (code "14") (name "LED3") (class "Default")
      (node (ref "R_LED3") (pin "2") (pinfunction "2_2") (pintype "passive"))
      (node (ref "U$3") (pin "84") (pinfunction "PD3_84") (pintype "bidirectional"))
    )
    (net (code "15") (name "LED4") (class "Default")
      (node (ref "R_LED4") (pin "2") (pinfunction "2_2") (pintype "passive"))
      (node (ref "U$3") (pin "85") (pinfunction "PD4_85") (pintype "bidirectional"))
    )
    (net (code "16") (name "LED5") (class "Default")
      (node (ref "R_LED5") (pin "2") (pinfunction "2_2") (pintype "passive"))
      (node (ref "U$3") (pin "86") (pinfunction "PD5_86") (pintype "bidirectional"))
    )
    (net (code "17") (name "LEFT_REC") (class "Default")
      (node (ref "L_REC") (pin "E") (pinfunction "E_E") (pintype "bidirectional"))
      (node (ref "R_L_R") (pin "2") (pinfunction "2_2") (pintype "passive"))
      (node (ref "U$3") (pin "32") (pinfunction "PC4_32") (pintype "bidirectional"))
    )
    (net (code "18") (name "LENCA") (class "Default")
      (node (ref "L_MOT") (pin "1") (pinfunction "1_1") (pintype "passive"))
      (node (ref "U$3") (pin "41") (pinfunction "PE11_41") (pintype "bidirectional"))
    )
    (net (code "19") (name "LENCB") (class "Default")
      (node (ref "L_MOT") (pin "2") (pinfunction "2_2") (pintype "passive"))
      (node (ref "U$3") (pin "39") (pinfunction "PE9_39") (pintype "bidirectional"))
    )
    (net (code "20") (name "LF_EMITTER") (class "Default")
      (node (ref "U$3") (pin "66") (pinfunction "PC9_66") (pintype "bidirectional"))
      (node (ref "U$9") (pin "7B") (pinfunction "7B_7B") (pintype "bidirectional"))
    )
    (net (code "21") (name "LF_REC") (class "Default")
      (node (ref "LF_REC") (pin "E") (pinfunction "E_E") (pintype "bidirectional"))
      (node (ref "R_LF_R") (pin "2") (pinfunction "2_2") (pintype "passive"))
      (node (ref "U$3") (pin "33") (pinfunction "PC5_33") (pintype "bidirectional"))
    )
    (net (code "22") (name "LPWMA") (class "Default")
      (node (ref "MOS_L") (pin "IN_A") (pinfunction "IN_A_IN_A") (pintype "bidirectional"))
      (node (ref "R1_LMOT") (pin "2") (pinfunction "2_2") (pintype "passive"))
      (node (ref "U$3") (pin "22") (pinfunction "PA0-WKUP_22") (pintype "bidirectional"))
    )
    (net (code "23") (name "LPWMB") (class "Default")
      (node (ref "MOS_L") (pin "IN_B") (pinfunction "IN_B_IN_B") (pintype "bidirectional"))
      (node (ref "R2_LMOT") (pin "2") (pinfunction "2_2") (pintype "passive"))
      (node (ref "U$3") (pin "23") (pinfunction "PA1_23") (pintype "bidirectional"))
    )
    (net (code "24") (name "L_EMITTER") (class "Default")
      (node (ref "U$3") (pin "65") (pinfunction "PC8_65") (pintype "bidirectional"))
      (node (ref "U$9") (pin "5B") (pinfunction "5B_5B") (pintype "bidirectional"))
      (node (ref "U$9") (pin "6B") (pinfunction "6B_6B") (pintype "bidirectional"))
    )
    (net (code "25") (name "Net-(33LDO-NR)") (class "Default")
      (node (ref "33LDO") (pin "4") (pinfunction "NR_4") (pintype "bidirectional"))
      (node (ref "C3_3.3V") (pin "1") (pinfunction "1_1") (pintype "passive"))
    )
    (net (code "26") (name "Net-(G1-AV_DD)") (class "Default")
      (node (ref "C2_G") (pin "1") (pinfunction "1_1") (pintype "passive"))
      (node (ref "G1") (pin "14") (pinfunction "AV_DD_14") (pintype "bidirectional"))
    )
    (net (code "27") (name "Net-(G1-CP5)") (class "Default")
      (node (ref "C3_G") (pin "1") (pinfunction "1_1") (pintype "passive"))
      (node (ref "D_G") (pin "C") (pinfunction "C_C") (pintype "passive"))
      (node (ref "G1") (pin "9") (pinfunction "CP5_9") (pintype "bidirectional"))
    )
    (net (code "28") (name "Net-(G1-DV_DD)") (class "Default")
      (node (ref "C1_G") (pin "1") (pinfunction "1_1") (pintype "passive"))
      (node (ref "G1") (pin "1") (pinfunction "DV_DD_1") (pintype "bidirectional"))
    )
    (net (code "29") (name "Net-(G1-V_X)") (class "Default")
      (node (ref "D_G") (pin "A") (pinfunction "A_A") (pintype "passive"))
      (node (ref "G1") (pin "8") (pinfunction "V_X_8") (pintype "bidirectional"))
      (node (ref "L4") (pin "2") (pinfunction "2_2") (pintype "passive"))
    )
    (net (code "30") (name "Net-(HB_L-PadN1D{slash}P1D)") (class "Default")
      (node (ref "HB_L") (pin "N1D/P1D") (pinfunction "N1D/P1D_N1D/P1D") (pintype "bidirectional"))
      (node (ref "L_MOT") (pin "5") (pinfunction "5_5") (pintype "passive"))
    )
    (net (code "31") (name "Net-(HB_L-PadN1G)") (class "Default")
      (node (ref "HB_L") (pin "N1G") (pinfunction "N1G_N1G") (pintype "bidirectional"))
      (node (ref "MOS_L") (pin "OUT_A") (pinfunction "OUT_A_OUT_A") (pintype "bidirectional"))
    )
    (net (code "32") (name "Net-(HB_L-PadN2D{slash}P2D)") (class "Default")
      (node (ref "HB_L") (pin "N2D/P2D") (pinfunction "N2D/P2D_N2D/P2D") (pintype "bidirectional"))
      (node (ref "L_MOT") (pin "6") (pinfunction "6_6") (pintype "passive"))
    )
    (net (code "33") (name "Net-(HB_L-PadN2G)") (class "Default")
      (node (ref "HB_L") (pin "N2G") (pinfunction "N2G_N2G") (pintype "bidirectional"))
      (node (ref "HB_L") (pin "P2G") (pinfunction "P2G_P2G") (pintype "bidirectional"))
      (node (ref "MOS_L") (pin "OUT_B") (pinfunction "OUT_B_OUT_B") (pintype "bidirectional"))
    )
    (net (code "34") (name "Net-(HB_R-PadN1D{slash}P1D)") (class "Default")
      (node (ref "HB_R") (pin "N1D/P1D") (pinfunction "N1D/P1D_N1D/P1D") (pintype "bidirectional"))
      (node (ref "R_MOT") (pin "5") (pinfunction "5_5") (pintype "passive"))
    )
    (net (code "35") (name "Net-(HB_R-PadN1G)") (class "Default")
      (node (ref "HB_R") (pin "N1G") (pinfunction "N1G_N1G") (pintype "bidirectional"))
      (node (ref "MOS_R") (pin "OUT_A") (pinfunction "OUT_A_OUT_A") (pintype "bidirectional"))
    )
    (net (code "36") (name "Net-(HB_R-PadN2D{slash}P2D)") (class "Default")
      (node (ref "HB_R") (pin "N2D/P2D") (pinfunction "N2D/P2D_N2D/P2D") (pintype "bidirectional"))
      (node (ref "R_MOT") (pin "6") (pinfunction "6_6") (pintype "passive"))
    )
    (net (code "37") (name "Net-(HB_R-PadN2G)") (class "Default")
      (node (ref "HB_R") (pin "N2G") (pinfunction "N2G_N2G") (pintype "bidirectional"))
      (node (ref "HB_R") (pin "P2G") (pinfunction "P2G_P2G") (pintype "bidirectional"))
      (node (ref "MOS_R") (pin "OUT_B") (pinfunction "OUT_B_OUT_B") (pintype "bidirectional"))
    )
    (net (code "38") (name "Net-(LED1-PadA)") (class "Default")
      (node (ref "LED1") (pin "A") (pinfunction "A_A") (pintype "passive"))
      (node (ref "R_LED1") (pin "1") (pinfunction "1_1") (pintype "passive"))
    )
    (net (code "39") (name "Net-(LED2-PadA)") (class "Default")
      (node (ref "LED2") (pin "A") (pinfunction "A_A") (pintype "passive"))
      (node (ref "R_LED2") (pin "1") (pinfunction "1_1") (pintype "passive"))
    )
    (net (code "40") (name "Net-(LED3-PadA)") (class "Default")
      (node (ref "LED3") (pin "A") (pinfunction "A_A") (pintype "passive"))
      (node (ref "R_LED3") (pin "1") (pinfunction "1_1") (pintype "passive"))
    )
    (net (code "41") (name "Net-(LED4-PadA)") (class "Default")
      (node (ref "LED4") (pin "A") (pinfunction "A_A") (pintype "passive"))
      (node (ref "R_LED4") (pin "1") (pinfunction "1_1") (pintype "passive"))
    )
    (net (code "42") (name "Net-(LED5-PadA)") (class "Default")
      (node (ref "LED5") (pin "A") (pinfunction "A_A") (pintype "passive"))
      (node (ref "R_LED5") (pin "1") (pinfunction "1_1") (pintype "passive"))
    )
    (net (code "43") (name "Net-(LF_IR_EMIT-C)") (class "Default")
      (node (ref "LF_IR_EMIT") (pin "K") (pinfunction "C_K") (pintype "passive"))
      (node (ref "R_LF_E") (pin "2") (pinfunction "2_2") (pintype "passive"))
    )
    (net (code "44") (name "Net-(L_IR_EMIT-C)") (class "Default")
      (node (ref "L_IR_EMIT") (pin "K") (pinfunction "C_K") (pintype "passive"))
      (node (ref "R_L_E") (pin "2") (pinfunction "2_2") (pintype "passive"))
    )
    (net (code "45") (name "Net-(PWR_LED-PadA)") (class "Default")
      (node (ref "PWR_LED") (pin "A") (pinfunction "A_A") (pintype "passive"))
      (node (ref "R_PWR") (pin "1") (pinfunction "1_1") (pintype "passive"))
    )
    (net (code "46") (name "Net-(PWR_SWITCH-Pad2)") (class "Default")
      (node (ref "PWR_SWITCH") (pin "2") (pinfunction "2_2") (pintype "bidirectional"))
      (node (ref "U$7") (pin "+") (pinfunction "+_+") (pintype "bidirectional"))
    )
    (net (code "47") (name "Net-(RF_IR_EMIT-C)") (class "Default")
      (node (ref "RF_IR_EMIT") (pin "K") (pinfunction "C_K") (pintype "passive"))
      (node (ref "R_RF_E") (pin "2") (pinfunction "2_2") (pintype "passive"))
    )
    (net (code "48") (name "Net-(R_IR_EMIT-C)") (class "Default")
      (node (ref "R_IR_EMIT") (pin "K") (pinfunction "C_K") (pintype "passive"))
      (node (ref "R_R_E") (pin "2") (pinfunction "2_2") (pintype "passive"))
    )
    (net (code "49") (name "Net-(R_LF_E-Pad1)") (class "Default")
      (node (ref "R_LF_E") (pin "1") (pinfunction "1_1") (pintype "passive"))
      (node (ref "U$9") (pin "3C") (pinfunction "3C_3C") (pintype "bidirectional"))
      (node (ref "U$9") (pin "4C") (pinfunction "4C_4C") (pintype "bidirectional"))
    )
    (net (code "50") (name "Net-(R_L_E-Pad1)") (class "Default")
      (node (ref "R_L_E") (pin "1") (pinfunction "1_1") (pintype "passive"))
      (node (ref "U$9") (pin "2C") (pinfunction "2C_2C") (pintype "bidirectional"))
    )
    (net (code "51") (name "Net-(R_RF_E-Pad1)") (class "Default")
      (node (ref "R_RF_E") (pin "1") (pinfunction "1_1") (pintype "passive"))
      (node (ref "U$9") (pin "5C") (pinfunction "5C_5C") (pintype "bidirectional"))
      (node (ref "U$9") (pin "6C") (pinfunction "6C_6C") (pintype "bidirectional"))
    )
    (net (code "52") (name "Net-(R_R_E-Pad1)") (class "Default")
      (node (ref "R_R_E") (pin "1") (pinfunction "1_1") (pintype "passive"))
      (node (ref "U$9") (pin "7C") (pinfunction "7C_7C") (pintype "bidirectional"))
    )
    (net (code "53") (name "Net-(SPK1--)") (class "Default")
      (node (ref "D_B") (pin "A") (pinfunction "A_A") (pintype "passive"))
      (node (ref "SPK1") (pin "+") (pinfunction "-_+") (pintype "passive"))
      (node (ref "U$9") (pin "1C") (pinfunction "1C_1C") (pintype "bidirectional"))
    )
    (net (code "54") (name "Net-(U$3-VCAP1)") (class "Default")
      (node (ref "C_VCAP1") (pin "1") (pinfunction "1_1") (pintype "passive"))
      (node (ref "U$3") (pin "48") (pinfunction "VCAP1_48") (pintype "bidirectional"))
    )
    (net (code "55") (name "Net-(U$3-VCAP2)") (class "Default")
      (node (ref "C_VCAP2") (pin "1") (pinfunction "1_1") (pintype "passive"))
      (node (ref "U$3") (pin "73") (pinfunction "VCAP2_73") (pintype "bidirectional"))
    )
    (net (code "56") (name "Net-(U$7-Pad-)") (class "Default")
      (node (ref "U$7") (pin "-") (pinfunction "-_-") (pintype "bidirectional"))
      (node (ref "U$8") (pin "+") (pinfunction "+_+") (pintype "bidirectional"))
    )
    (net (code "57") (name "RENCA") (class "Default")
      (node (ref "R_MOT") (pin "1") (pinfunction "1_1") (pintype "passive"))
      (node (ref "U$3") (pin "44") (pinfunction "PE14_44") (pintype "bidirectional"))
    )
    (net (code "58") (name "RENCB") (class "Default")
      (node (ref "R_MOT") (pin "2") (pinfunction "2_2") (pintype "passive"))
      (node (ref "U$3") (pin "43") (pinfunction "PE13_43") (pintype "bidirectional"))
    )
    (net (code "59") (name "RESET") (class "Default")
      (node (ref "C_RESET1") (pin "1") (pinfunction "1_1") (pintype "passive"))
      (node (ref "RST") (pin "1") (pinfunction "S_1") (pintype "passive"))
      (node (ref "R_RST_UP1") (pin "1") (pinfunction "1_1") (pintype "passive"))
      (node (ref "U$3") (pin "14") (pinfunction "NRST_14") (pintype "bidirectional"))
    )
    (net (code "60") (name "RF_EMITTER") (class "Default")
      (node (ref "U$3") (pin "91") (pinfunction "PB5_91") (pintype "bidirectional"))
      (node (ref "U$9") (pin "2B") (pinfunction "2B_2B") (pintype "bidirectional"))
    )
    (net (code "61") (name "RF_REC") (class "Default")
      (node (ref "RF_REC") (pin "E") (pinfunction "E_E") (pintype "bidirectional"))
      (node (ref "R_RF_R") (pin "2") (pinfunction "2_2") (pintype "passive"))
      (node (ref "U$3") (pin "34") (pinfunction "PB0_34") (pintype "bidirectional"))
    )
    (net (code "62") (name "RIGHT_REC") (class "Default")
      (node (ref "R_REC") (pin "E") (pinfunction "E_E") (pintype "bidirectional"))
      (node (ref "R_R_R") (pin "2") (pinfunction "2_2") (pintype "passive"))
      (node (ref "U$3") (pin "35") (pinfunction "PB1_35") (pintype "bidirectional"))
    )
    (net (code "63") (name "RPWMA") (class "Default")
      (node (ref "MOS_R") (pin "IN_A") (pinfunction "IN_A_IN_A") (pintype "bidirectional"))
      (node (ref "R1_RMOT") (pin "2") (pinfunction "2_2") (pintype "passive"))
      (node (ref "U$3") (pin "24") (pinfunction "PA2_24") (pintype "bidirectional"))
    )
    (net (code "64") (name "RPWMB") (class "Default")
      (node (ref "MOS_R") (pin "IN_B") (pinfunction "IN_B_IN_B") (pintype "bidirectional"))
      (node (ref "R2_RMOT") (pin "2") (pinfunction "2_2") (pintype "passive"))
      (node (ref "U$3") (pin "25") (pinfunction "PA3_25") (pintype "bidirectional"))
    )
    (net (code "65") (name "RX") (class "Default")
      (node (ref "PROG_HEAD") (pin "5") (pinfunction "5_5") (pintype "passive"))
      (node (ref "U$3") (pin "69") (pinfunction "PA10_69") (pintype "bidirectional"))
    )
    (net (code "66") (name "R_EMITTER") (class "Default")
      (node (ref "U$3") (pin "90") (pinfunction "PB4_90") (pintype "bidirectional"))
      (node (ref "U$9") (pin "3B") (pinfunction "3B_3B") (pintype "bidirectional"))
      (node (ref "U$9") (pin "4B") (pinfunction "4B_4B") (pintype "bidirectional"))
    )
    (net (code "67") (name "SW1") (class "Default")
      (node (ref "C_S1") (pin "1") (pinfunction "1_1") (pintype "passive"))
      (node (ref "R_SW1") (pin "1") (pinfunction "1_1") (pintype "passive"))
      (node (ref "S1") (pin "1") (pinfunction "S_1") (pintype "passive"))
      (node (ref "U$3") (pin "63") (pinfunction "PC6_63") (pintype "bidirectional"))
    )
    (net (code "68") (name "SW2") (class "Default")
      (node (ref "C_S2") (pin "1") (pinfunction "1_1") (pintype "passive"))
      (node (ref "R_SW2") (pin "1") (pinfunction "1_1") (pintype "passive"))
      (node (ref "S2") (pin "1") (pinfunction "S_1") (pintype "passive"))
      (node (ref "U$3") (pin "62") (pinfunction "PD15_62") (pintype "bidirectional"))
    )
    (net (code "69") (name "SWCLK") (class "Default")
      (node (ref "PROG_HEAD") (pin "6") (pinfunction "6_6") (pintype "passive"))
      (node (ref "U$3") (pin "76") (pinfunction "PA14_76") (pintype "bidirectional"))
    )
    (net (code "70") (name "SWDIO") (class "Default")
      (node (ref "PROG_HEAD") (pin "8") (pinfunction "8_8") (pintype "passive"))
      (node (ref "U$3") (pin "72") (pinfunction "PA13_72") (pintype "bidirectional"))
    )
    (net (code "71") (name "TX") (class "Default")
      (node (ref "PROG_HEAD") (pin "7") (pinfunction "7_7") (pintype "passive"))
      (node (ref "U$3") (pin "68") (pinfunction "PA9_68") (pintype "bidirectional"))
    )
    (net (code "72") (name "VOLTMETER") (class "Default")
      (node (ref "R1_VOLT") (pin "1") (pinfunction "1_1") (pintype "passive"))
      (node (ref "R2_VOLT") (pin "2") (pinfunction "2_2") (pintype "passive"))
      (node (ref "U$3") (pin "15") (pinfunction "PC0_15") (pintype "bidirectional"))
    )
    (net (code "73") (name "V_BAT") (class "Default")
      (node (ref "50LDO") (pin "IN1") (pinfunction "IN1_IN1") (pintype "bidirectional"))
      (node (ref "50LDO") (pin "IN2") (pinfunction "IN2_IN2") (pintype "bidirectional"))
      (node (ref "C1_LMOT") (pin "2") (pinfunction "2_2") (pintype "passive"))
      (node (ref "C1_RMOT") (pin "2") (pinfunction "2_2") (pintype "passive"))
      (node (ref "C2_LMOT") (pin "2") (pinfunction "2_2") (pintype "passive"))
      (node (ref "C2_RMOT") (pin "2") (pinfunction "2_2") (pintype "passive"))
      (node (ref "C_VBAT1") (pin "1") (pinfunction "1_1") (pintype "passive"))
      (node (ref "C_VBAT2") (pin "1") (pinfunction "1_1") (pintype "passive"))
      (node (ref "HB_L") (pin "P1S/PS2") (pinfunction "P1S/P2S_P1S/PS2") (pintype "bidirectional"))
      (node (ref "HB_R") (pin "P1S/PS2") (pinfunction "P1S/P2S_P1S/PS2") (pintype "bidirectional"))
      (node (ref "MOS_L") (pin "VDD") (pinfunction "VDD_VDD") (pintype "bidirectional"))
      (node (ref "MOS_R") (pin "VDD") (pinfunction "VDD_VDD") (pintype "bidirectional"))
      (node (ref "PWR_SWITCH") (pin "3") (pinfunction "3_3") (pintype "bidirectional"))
      (node (ref "R1_VOLT") (pin "2") (pinfunction "2_2") (pintype "passive"))
    )
    (net (code "74") (name "unconnected-(50LDO-PadNC)") (class "Default")
      (node (ref "50LDO") (pin "NC") (pinfunction "NC_NC") (pintype "bidirectional"))
    )
    (net (code "75") (name "unconnected-(50LDO-PadPG)") (class "Default")
      (node (ref "50LDO") (pin "PG") (pinfunction "PG_PG") (pintype "bidirectional"))
    )
    (net (code "76") (name "unconnected-(BOOT0-P1-Pad4)") (class "Default")
      (node (ref "BOOT0") (pin "4") (pinfunction "P1_4") (pintype "passive"))
    )
    (net (code "77") (name "unconnected-(BOOT0-S1-Pad2)") (class "Default")
      (node (ref "BOOT0") (pin "2") (pinfunction "S1_2") (pintype "passive"))
    )
    (net (code "78") (name "unconnected-(HB_L-PadP1G)") (class "Default")
      (node (ref "HB_L") (pin "P1G") (pinfunction "P1G_P1G") (pintype "bidirectional"))
    )
    (net (code "79") (name "unconnected-(HB_R-PadP1G)") (class "Default")
      (node (ref "HB_R") (pin "P1G") (pinfunction "P1G_P1G") (pintype "bidirectional"))
    )
    (net (code "80") (name "unconnected-(MOS_L-PadNC1)") (class "Default")
      (node (ref "MOS_L") (pin "NC1") (pinfunction "NC1_NC1") (pintype "bidirectional"))
    )
    (net (code "81") (name "unconnected-(MOS_L-PadNC2)") (class "Default")
      (node (ref "MOS_L") (pin "NC2") (pinfunction "NC2_NC2") (pintype "bidirectional"))
    )
    (net (code "82") (name "unconnected-(MOS_R-PadNC1)") (class "Default")
      (node (ref "MOS_R") (pin "NC1") (pinfunction "NC1_NC1") (pintype "bidirectional"))
    )
    (net (code "83") (name "unconnected-(MOS_R-PadNC2)") (class "Default")
      (node (ref "MOS_R") (pin "NC2") (pinfunction "NC2_NC2") (pintype "bidirectional"))
    )
    (net (code "84") (name "unconnected-(PWR_SWITCH-Pad1)") (class "Default")
      (node (ref "PWR_SWITCH") (pin "1") (pinfunction "1_1") (pintype "bidirectional"))
    )
    (net (code "85") (name "unconnected-(RST-P1-Pad4)") (class "Default")
      (node (ref "RST") (pin "4") (pinfunction "P1_4") (pintype "passive"))
    )
    (net (code "86") (name "unconnected-(RST-S1-Pad2)") (class "Default")
      (node (ref "RST") (pin "2") (pinfunction "S1_2") (pintype "passive"))
    )
    (net (code "87") (name "unconnected-(S1-P1-Pad4)") (class "Default")
      (node (ref "S1") (pin "4") (pinfunction "P1_4") (pintype "passive"))
    )
    (net (code "88") (name "unconnected-(S1-S1-Pad2)") (class "Default")
      (node (ref "S1") (pin "2") (pinfunction "S1_2") (pintype "passive"))
    )
    (net (code "89") (name "unconnected-(S2-P1-Pad4)") (class "Default")
      (node (ref "S2") (pin "4") (pinfunction "P1_4") (pintype "passive"))
    )
    (net (code "90") (name "unconnected-(S2-S1-Pad2)") (class "Default")
      (node (ref "S2") (pin "2") (pinfunction "S1_2") (pintype "passive"))
    )
    (net (code "91") (name "unconnected-(U$3-PA8-Pad67)") (class "Default")
      (node (ref "U$3") (pin "67") (pinfunction "PA8_67") (pintype "bidirectional"))
    )
    (net (code "92") (name "unconnected-(U$3-PA11-Pad70)") (class "Default")
      (node (ref "U$3") (pin "70") (pinfunction "PA11_70") (pintype "bidirectional"))
    )
    (net (code "93") (name "unconnected-(U$3-PA12-Pad71)") (class "Default")
      (node (ref "U$3") (pin "71") (pinfunction "PA12_71") (pintype "bidirectional"))
    )
    (net (code "94") (name "unconnected-(U$3-PA15-Pad77)") (class "Default")
      (node (ref "U$3") (pin "77") (pinfunction "PA15_77") (pintype "bidirectional"))
    )
    (net (code "95") (name "unconnected-(U$3-PB2-Pad36)") (class "Default")
      (node (ref "U$3") (pin "36") (pinfunction "PB2_36") (pintype "bidirectional"))
    )
    (net (code "96") (name "unconnected-(U$3-PB3-Pad89)") (class "Default")
      (node (ref "U$3") (pin "89") (pinfunction "PB3_89") (pintype "bidirectional"))
    )
    (net (code "97") (name "unconnected-(U$3-PB6-Pad92)") (class "Default")
      (node (ref "U$3") (pin "92") (pinfunction "PB6_92") (pintype "bidirectional"))
    )
    (net (code "98") (name "unconnected-(U$3-PB7-Pad93)") (class "Default")
      (node (ref "U$3") (pin "93") (pinfunction "PB7_93") (pintype "bidirectional"))
    )
    (net (code "99") (name "unconnected-(U$3-PB8-Pad95)") (class "Default")
      (node (ref "U$3") (pin "95") (pinfunction "PB8_95") (pintype "bidirectional"))
    )
    (net (code "100") (name "unconnected-(U$3-PB9-Pad96)") (class "Default")
      (node (ref "U$3") (pin "96") (pinfunction "PB9_96") (pintype "bidirectional"))
    )
    (net (code "101") (name "unconnected-(U$3-PB10-Pad46)") (class "Default")
      (node (ref "U$3") (pin "46") (pinfunction "PB10_46") (pintype "bidirectional"))
    )
    (net (code "102") (name "unconnected-(U$3-PB11-Pad47)") (class "Default")
      (node (ref "U$3") (pin "47") (pinfunction "PB11_47") (pintype "bidirectional"))
    )
    (net (code "103") (name "unconnected-(U$3-PB12-Pad51)") (class "Default")
      (node (ref "U$3") (pin "51") (pinfunction "PB12_51") (pintype "bidirectional"))
    )
    (net (code "104") (name "unconnected-(U$3-PB13-Pad52)") (class "Default")
      (node (ref "U$3") (pin "52") (pinfunction "PB13_52") (pintype "bidirectional"))
    )
    (net (code "105") (name "unconnected-(U$3-PB14-Pad53)") (class "Default")
      (node (ref "U$3") (pin "53") (pinfunction "PB14_53") (pintype "bidirectional"))
    )
    (net (code "106") (name "unconnected-(U$3-PB15-Pad54)") (class "Default")
      (node (ref "U$3") (pin "54") (pinfunction "PB15_54") (pintype "bidirectional"))
    )
    (net (code "107") (name "unconnected-(U$3-PC1-Pad16)") (class "Default")
      (node (ref "U$3") (pin "16") (pinfunction "PC1_16") (pintype "bidirectional"))
    )
    (net (code "108") (name "unconnected-(U$3-PC2-Pad17)") (class "Default")
      (node (ref "U$3") (pin "17") (pinfunction "PC2_17") (pintype "bidirectional"))
    )
    (net (code "109") (name "unconnected-(U$3-PC3-Pad18)") (class "Default")
      (node (ref "U$3") (pin "18") (pinfunction "PC3_18") (pintype "bidirectional"))
    )
    (net (code "110") (name "unconnected-(U$3-PC7-Pad64)") (class "Default")
      (node (ref "U$3") (pin "64") (pinfunction "PC7_64") (pintype "bidirectional"))
    )
    (net (code "111") (name "unconnected-(U$3-PC10-Pad78)") (class "Default")
      (node (ref "U$3") (pin "78") (pinfunction "PC10_78") (pintype "bidirectional"))
    )
    (net (code "112") (name "unconnected-(U$3-PC11-Pad79)") (class "Default")
      (node (ref "U$3") (pin "79") (pinfunction "PC11_79") (pintype "bidirectional"))
    )
    (net (code "113") (name "unconnected-(U$3-PC12-Pad80)") (class "Default")
      (node (ref "U$3") (pin "80") (pinfunction "PC12_80") (pintype "bidirectional"))
    )
    (net (code "114") (name "unconnected-(U$3-PC13-ANTI_TAMP-Pad7)") (class "Default")
      (node (ref "U$3") (pin "7") (pinfunction "PC13-ANTI_TAMP_7") (pintype "bidirectional"))
    )
    (net (code "115") (name "unconnected-(U$3-PC14-OSC32_IN-Pad8)") (class "Default")
      (node (ref "U$3") (pin "8") (pinfunction "PC14-OSC32_IN_8") (pintype "bidirectional"))
    )
    (net (code "116") (name "unconnected-(U$3-PC15-OSC32_OUT-Pad9)") (class "Default")
      (node (ref "U$3") (pin "9") (pinfunction "PC15-OSC32_OUT_9") (pintype "bidirectional"))
    )
    (net (code "117") (name "unconnected-(U$3-PD0-Pad81)") (class "Default")
      (node (ref "U$3") (pin "81") (pinfunction "PD0_81") (pintype "bidirectional"))
    )
    (net (code "118") (name "unconnected-(U$3-PD6-Pad87)") (class "Default")
      (node (ref "U$3") (pin "87") (pinfunction "PD6_87") (pintype "bidirectional"))
    )
    (net (code "119") (name "unconnected-(U$3-PD7-Pad88)") (class "Default")
      (node (ref "U$3") (pin "88") (pinfunction "PD7_88") (pintype "bidirectional"))
    )
    (net (code "120") (name "unconnected-(U$3-PD8-Pad55)") (class "Default")
      (node (ref "U$3") (pin "55") (pinfunction "PD8_55") (pintype "bidirectional"))
    )
    (net (code "121") (name "unconnected-(U$3-PD9-Pad56)") (class "Default")
      (node (ref "U$3") (pin "56") (pinfunction "PD9_56") (pintype "bidirectional"))
    )
    (net (code "122") (name "unconnected-(U$3-PD10-Pad57)") (class "Default")
      (node (ref "U$3") (pin "57") (pinfunction "PD10_57") (pintype "bidirectional"))
    )
    (net (code "123") (name "unconnected-(U$3-PD11-Pad58)") (class "Default")
      (node (ref "U$3") (pin "58") (pinfunction "PD11_58") (pintype "bidirectional"))
    )
    (net (code "124") (name "unconnected-(U$3-PD13-Pad60)") (class "Default")
      (node (ref "U$3") (pin "60") (pinfunction "PD13_60") (pintype "bidirectional"))
    )
    (net (code "125") (name "unconnected-(U$3-PD14-Pad61)") (class "Default")
      (node (ref "U$3") (pin "61") (pinfunction "PD14_61") (pintype "bidirectional"))
    )
    (net (code "126") (name "unconnected-(U$3-PE0-Pad97)") (class "Default")
      (node (ref "U$3") (pin "97") (pinfunction "PE0_97") (pintype "bidirectional"))
    )
    (net (code "127") (name "unconnected-(U$3-PE1-Pad98)") (class "Default")
      (node (ref "U$3") (pin "98") (pinfunction "PE1_98") (pintype "bidirectional"))
    )
    (net (code "128") (name "unconnected-(U$3-PE2-Pad1)") (class "Default")
      (node (ref "U$3") (pin "1") (pinfunction "PE2_1") (pintype "bidirectional"))
    )
    (net (code "129") (name "unconnected-(U$3-PE3-Pad2)") (class "Default")
      (node (ref "U$3") (pin "2") (pinfunction "PE3_2") (pintype "bidirectional"))
    )
    (net (code "130") (name "unconnected-(U$3-PE4-Pad3)") (class "Default")
      (node (ref "U$3") (pin "3") (pinfunction "PE4_3") (pintype "bidirectional"))
    )
    (net (code "131") (name "unconnected-(U$3-PE5-Pad4)") (class "Default")
      (node (ref "U$3") (pin "4") (pinfunction "PE5_4") (pintype "bidirectional"))
    )
    (net (code "132") (name "unconnected-(U$3-PE6-Pad5)") (class "Default")
      (node (ref "U$3") (pin "5") (pinfunction "PE6_5") (pintype "bidirectional"))
    )
    (net (code "133") (name "unconnected-(U$3-PE7-Pad37)") (class "Default")
      (node (ref "U$3") (pin "37") (pinfunction "PE7_37") (pintype "bidirectional"))
    )
    (net (code "134") (name "unconnected-(U$3-PE8-Pad38)") (class "Default")
      (node (ref "U$3") (pin "38") (pinfunction "PE8_38") (pintype "bidirectional"))
    )
    (net (code "135") (name "unconnected-(U$3-PE10-Pad40)") (class "Default")
      (node (ref "U$3") (pin "40") (pinfunction "PE10_40") (pintype "bidirectional"))
    )
    (net (code "136") (name "unconnected-(U$3-PE12-Pad42)") (class "Default")
      (node (ref "U$3") (pin "42") (pinfunction "PE12_42") (pintype "bidirectional"))
    )
    (net (code "137") (name "unconnected-(U$3-PE15-Pad45)") (class "Default")
      (node (ref "U$3") (pin "45") (pinfunction "PE15_45") (pintype "bidirectional"))
    )
    (net (code "138") (name "unconnected-(U$3-PH0-OSC_IN-Pad12)") (class "Default")
      (node (ref "U$3") (pin "12") (pinfunction "PH0-OSC_IN_12") (pintype "bidirectional"))
    )
    (net (code "139") (name "unconnected-(U$3-PH1-OSC_OUT-Pad13)") (class "Default")
      (node (ref "U$3") (pin "13") (pinfunction "PH1-OSC_OUT_13") (pintype "bidirectional"))
    )
    (net (code "140") (name "unconnected-(U$9-PadCOM)") (class "Default")
      (node (ref "U$9") (pin "COM") (pinfunction "COM_COM") (pintype "bidirectional"))
    )
  )
)
